# clouds_v30.net
KiCad netlist of a schematic drawn in EAGLE
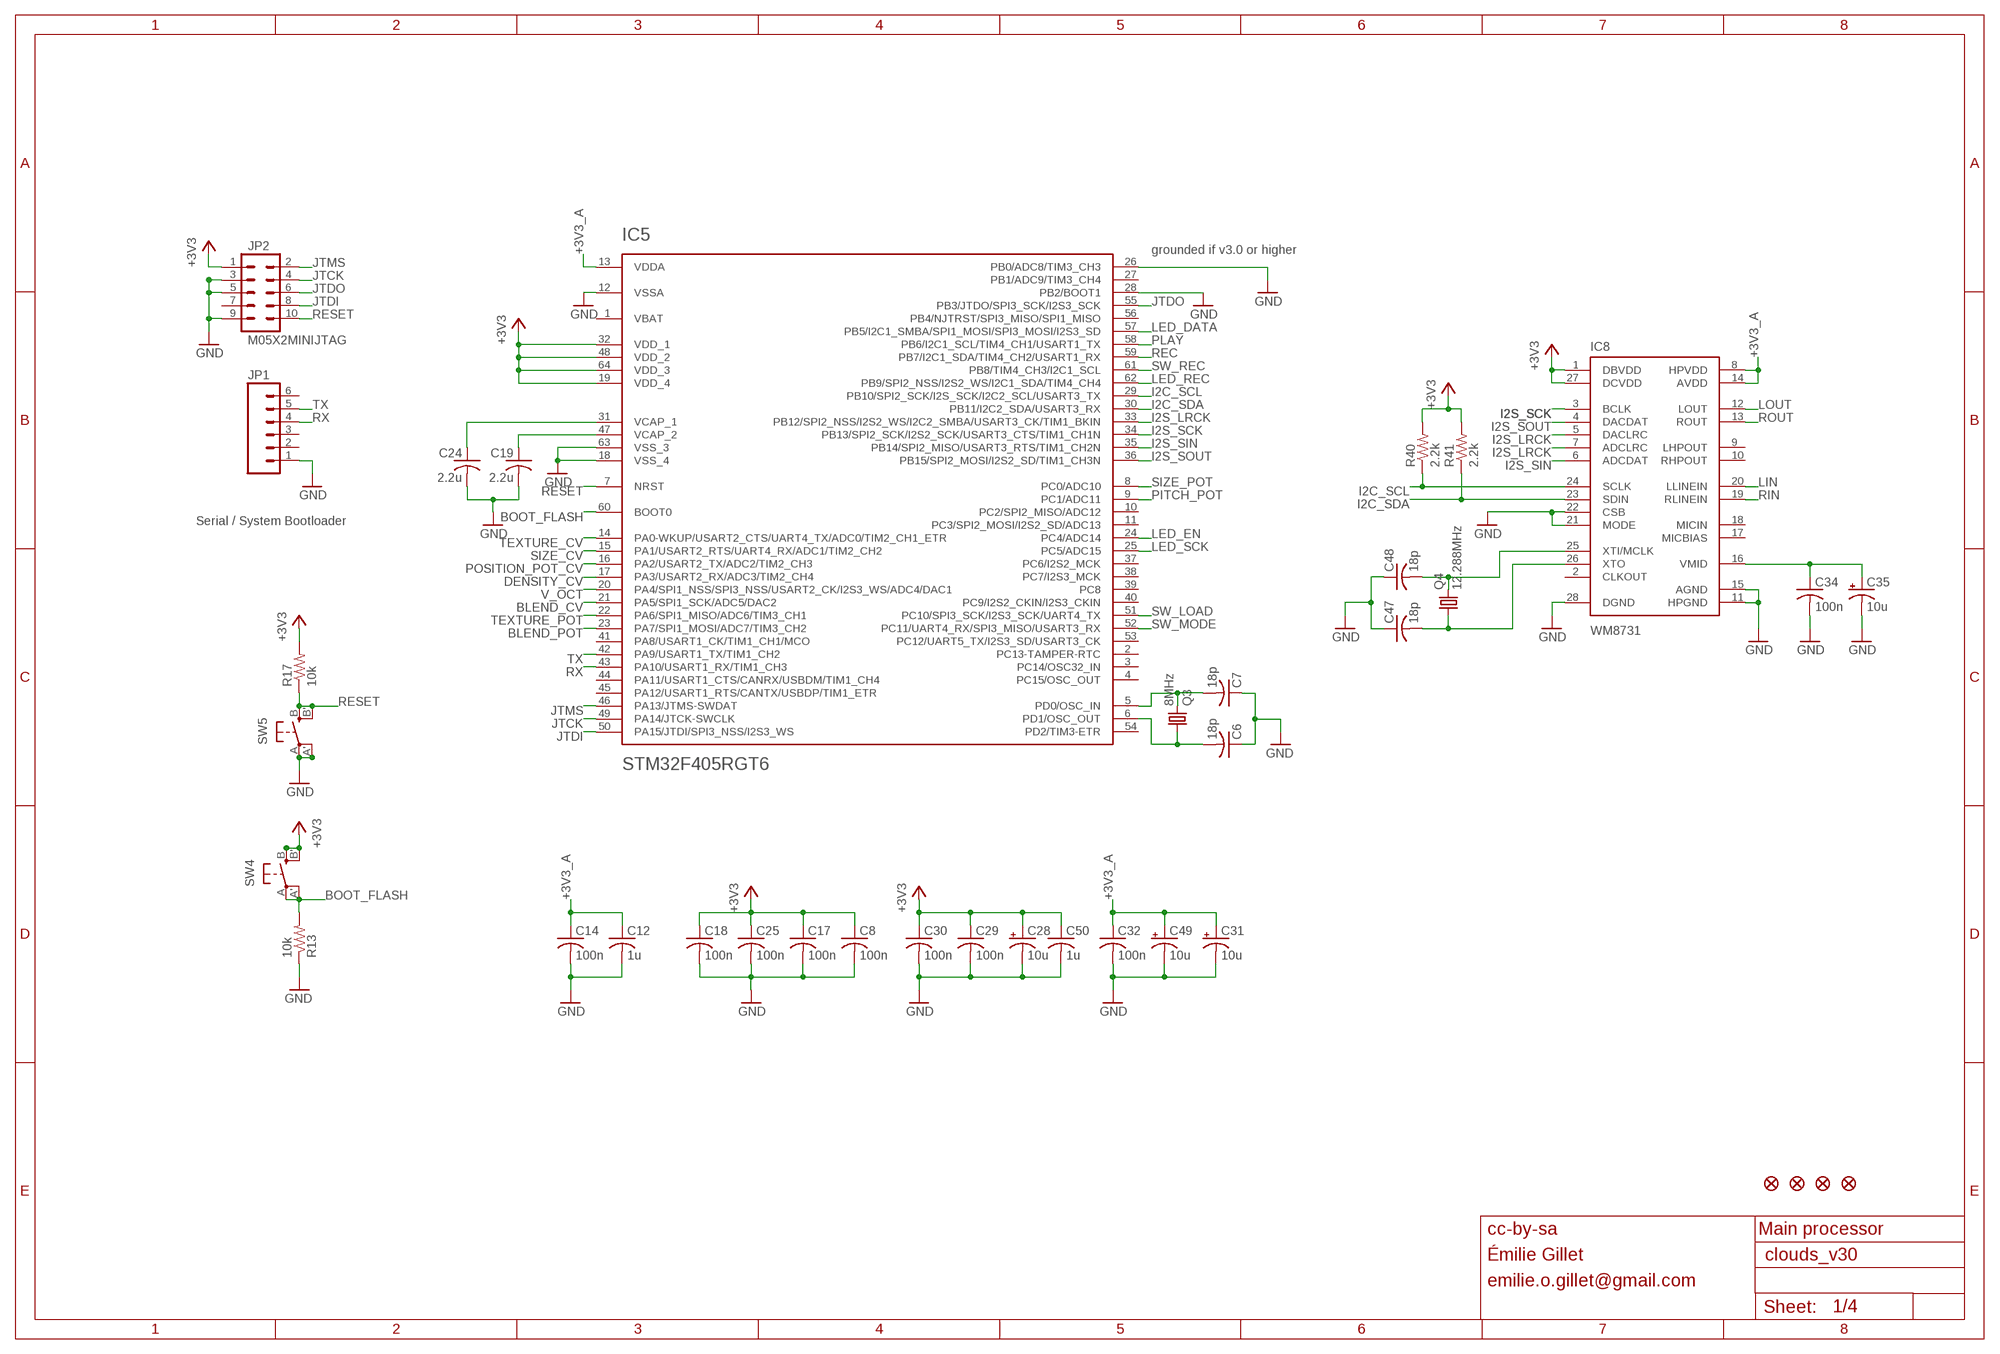
[diagram p0: schematic, sheet 1]
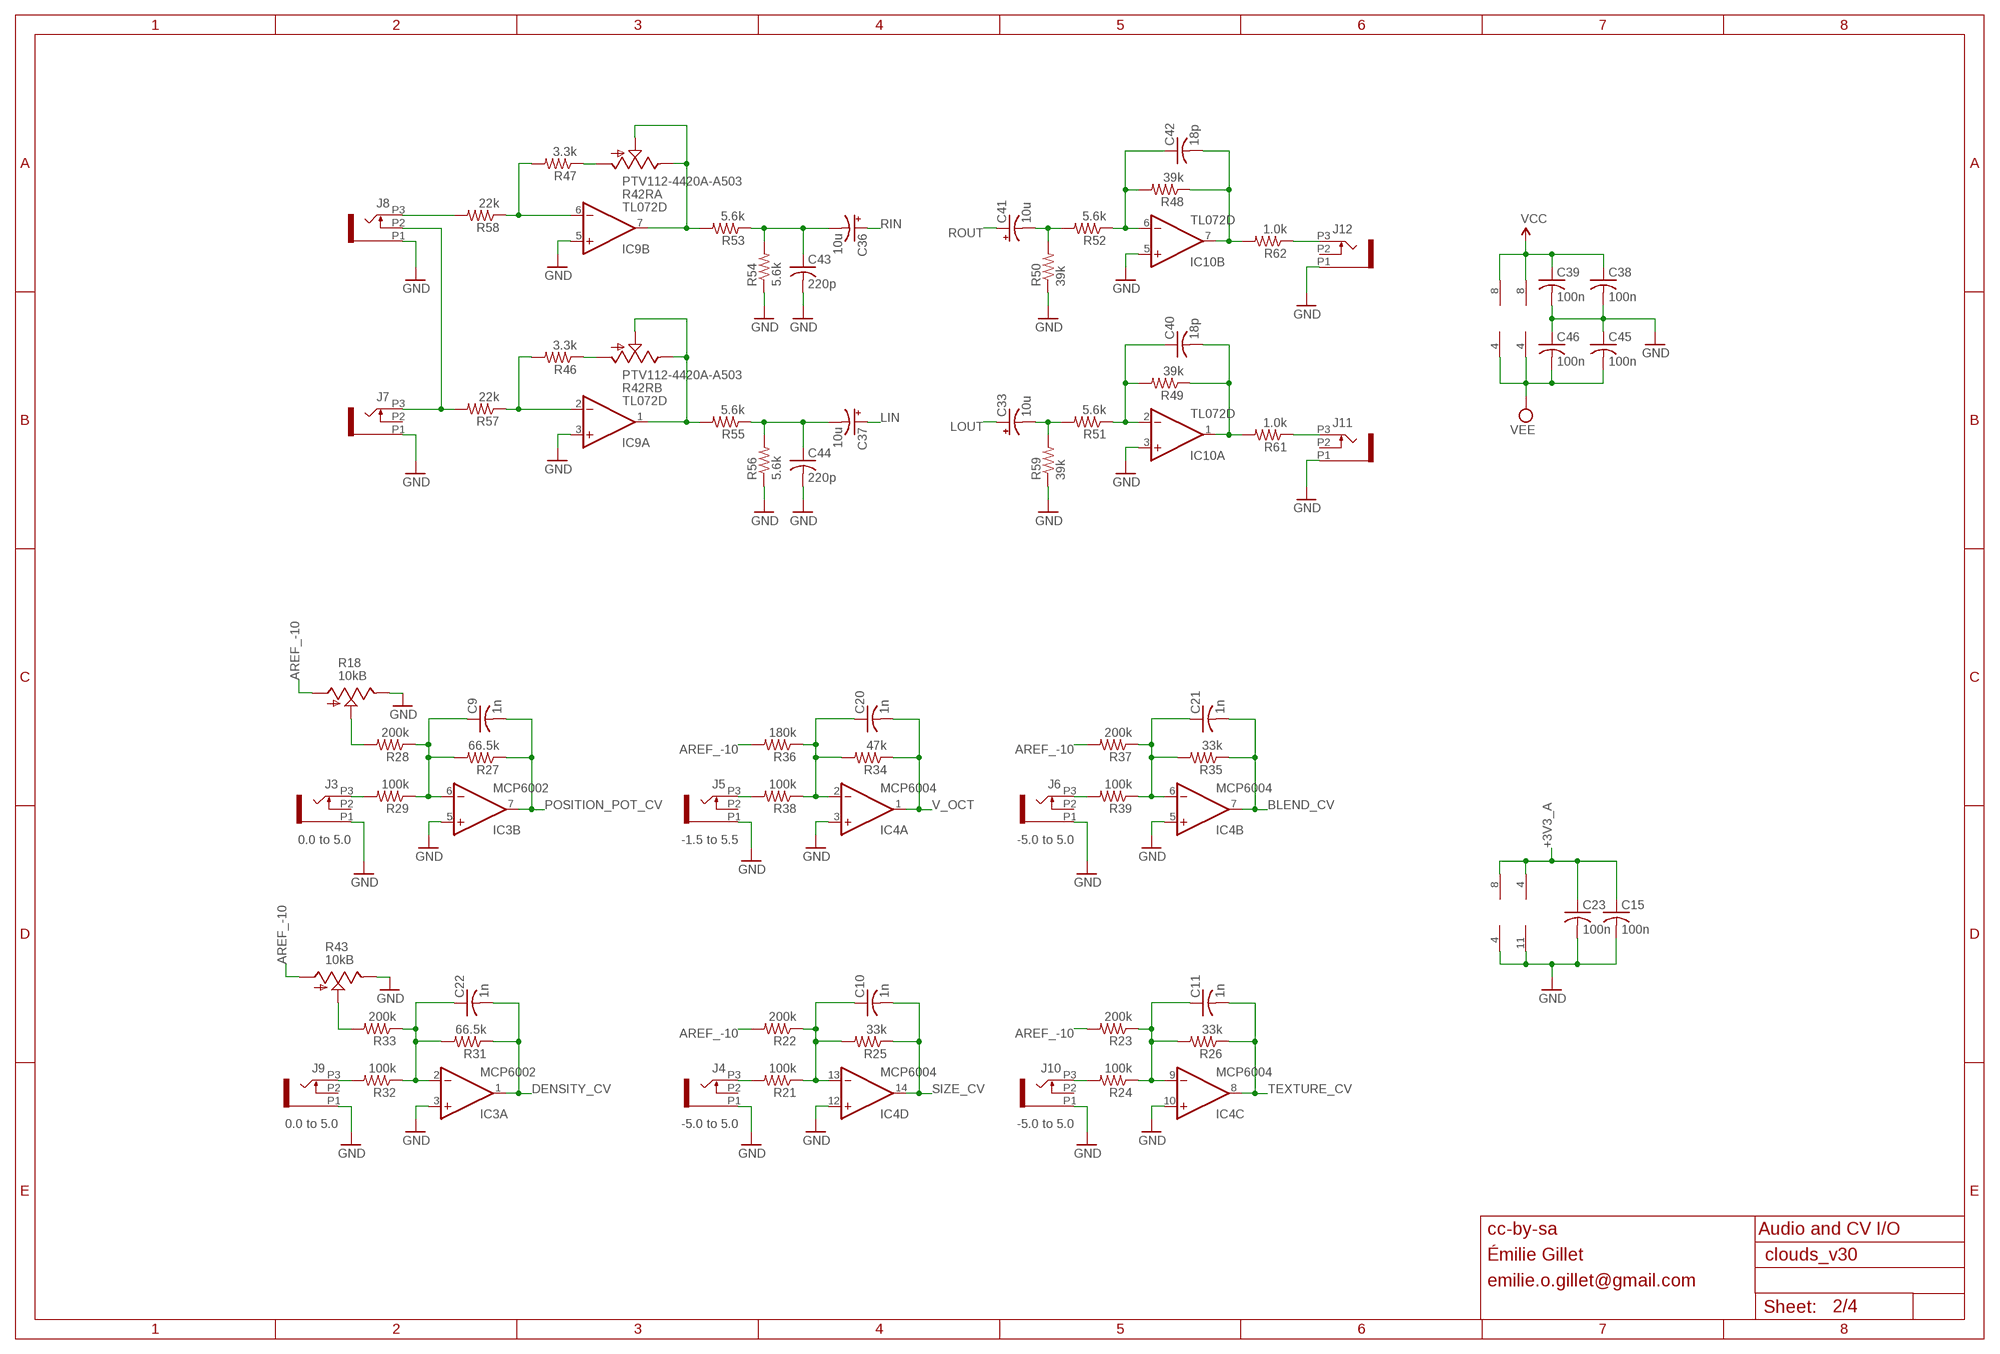
[diagram p1: schematic, sheet 2]
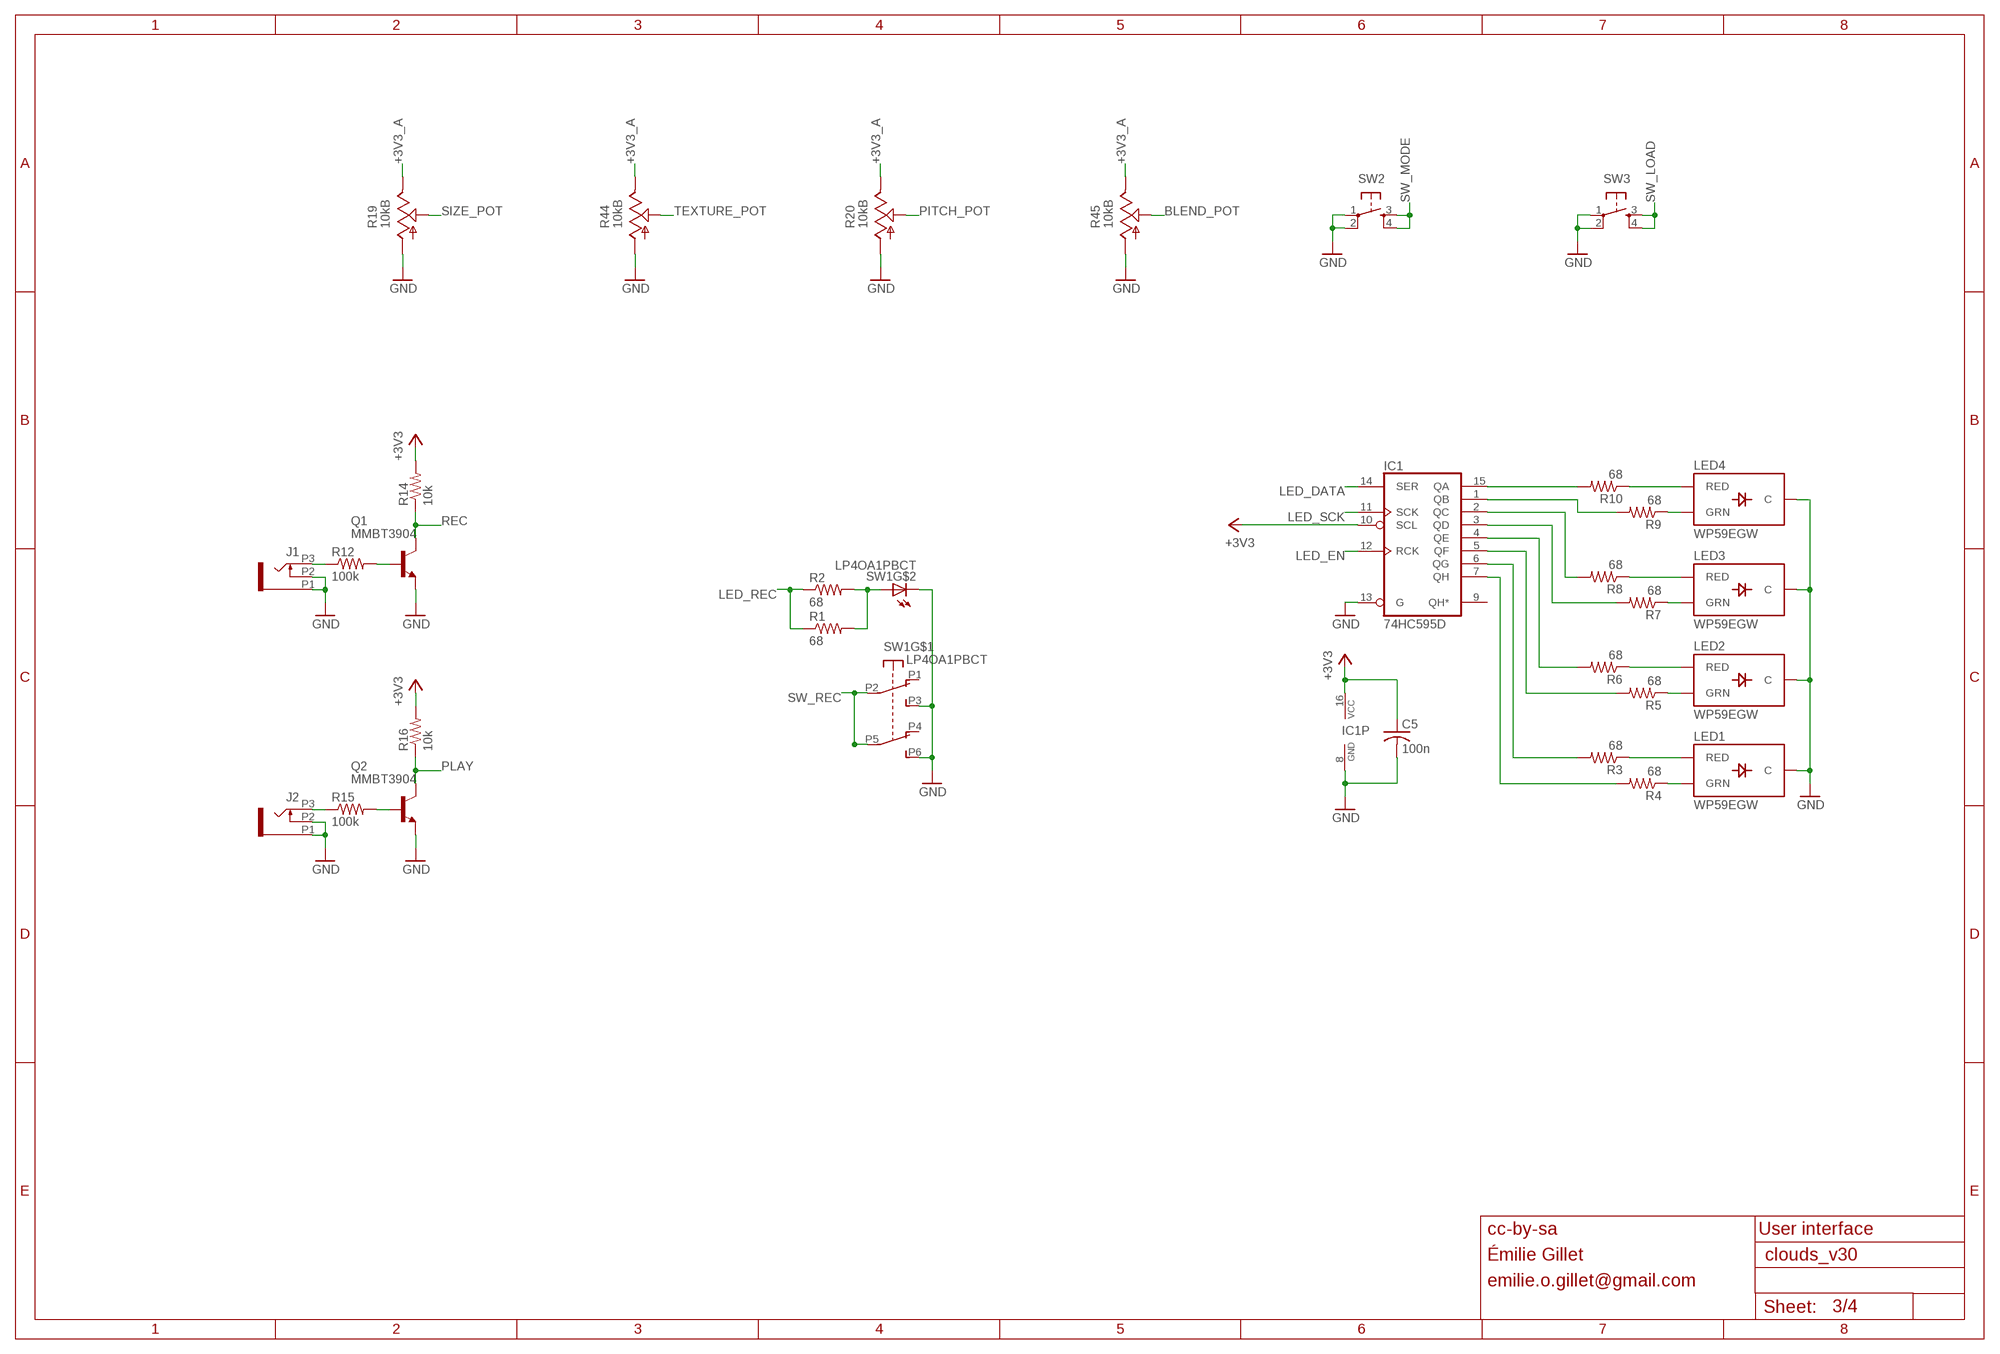
[diagram p2: schematic, sheet 3]
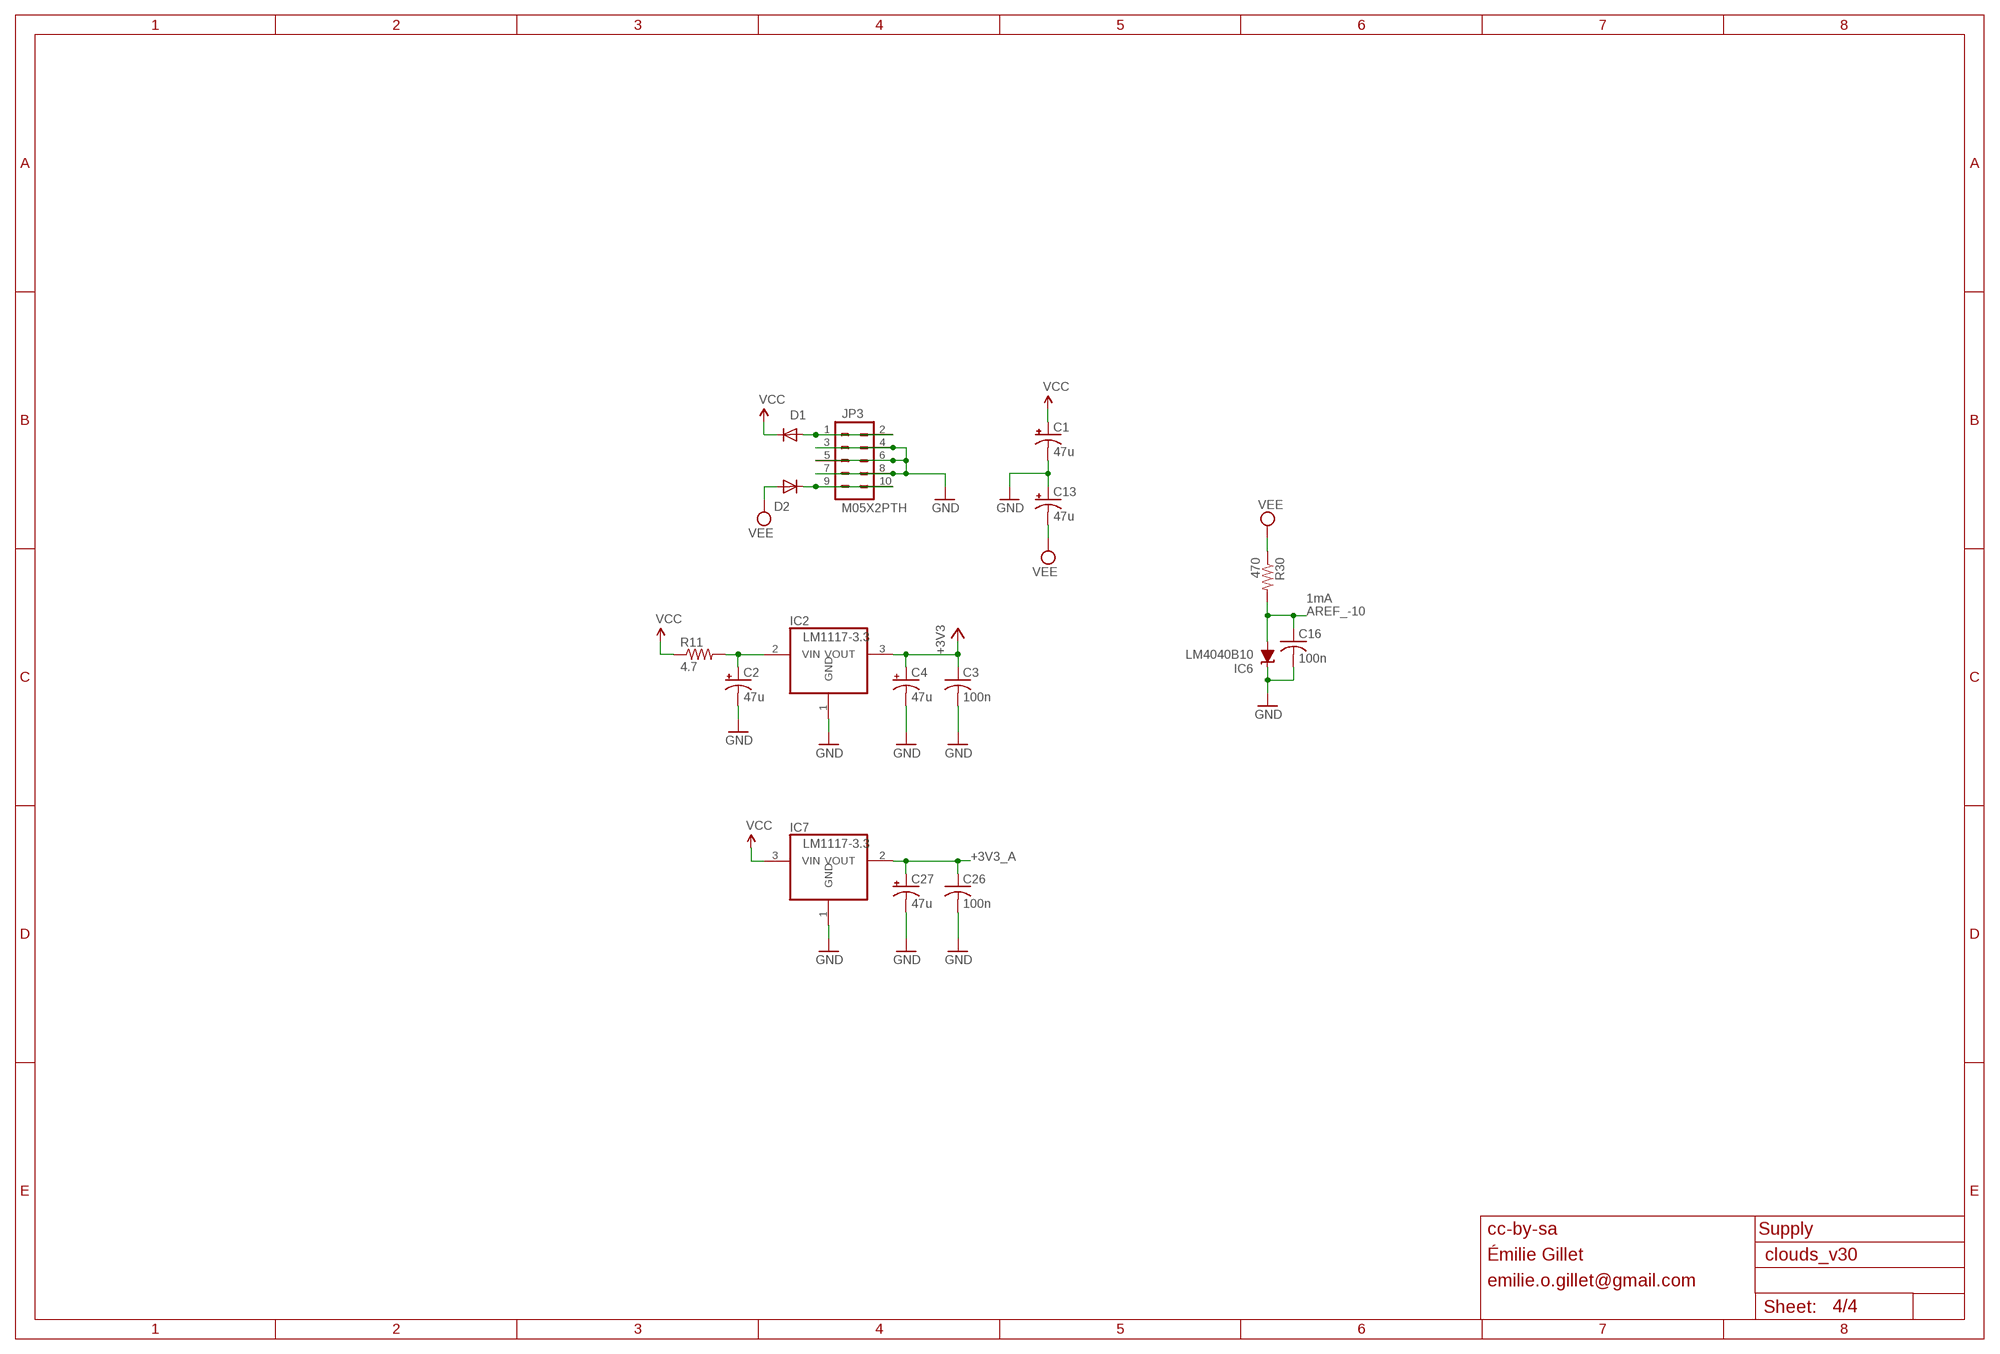
[diagram p3: schematic, sheet 4]

(export (version "E")
  (design (tool "Eeschema 10.0.6"))
  (components
    (comp (ref "C9")
      (value "1n")
      (footprint "eagle-import:C0603")
      (libsource (lib "eagle-import") (part "C-USC0603"))
    )
    (comp (ref "C10")
      (value "1n")
      (footprint "eagle-import:C0603")
      (libsource (lib "eagle-import") (part "C-USC0603"))
    )
    (comp (ref "C11")
      (value "1n")
      (footprint "eagle-import:C0603")
      (libsource (lib "eagle-import") (part "C-USC0603"))
    )
    (comp (ref "C15")
      (value "100n")
      (footprint "eagle-import:C0603")
      (libsource (lib "eagle-import") (part "C-USC0603"))
    )
    (comp (ref "C20")
      (value "1n")
      (footprint "eagle-import:C0603")
      (libsource (lib "eagle-import") (part "C-USC0603"))
    )
    (comp (ref "C21")
      (value "1n")
      (footprint "eagle-import:C0603")
      (libsource (lib "eagle-import") (part "C-USC0603"))
    )
    (comp (ref "C22")
      (value "1n")
      (footprint "eagle-import:C0603")
      (libsource (lib "eagle-import") (part "C-USC0603"))
    )
    (comp (ref "C23")
      (value "100n")
      (footprint "eagle-import:C0603")
      (libsource (lib "eagle-import") (part "C-USC0603"))
    )
    (comp (ref "C33")
      (value "10u")
      (footprint "eagle-import:PANASONIC_B")
      (libsource (lib "eagle-import") (part "CPOL-USB"))
    )
    (comp (ref "C36")
      (value "10u")
      (footprint "eagle-import:PANASONIC_B")
      (libsource (lib "eagle-import") (part "CPOL-USB"))
    )
    (comp (ref "C37")
      (value "10u")
      (footprint "eagle-import:PANASONIC_B")
      (libsource (lib "eagle-import") (part "CPOL-USB"))
    )
    (comp (ref "C38")
      (value "100n")
      (footprint "eagle-import:C0603")
      (libsource (lib "eagle-import") (part "C-USC0603"))
    )
    (comp (ref "C39")
      (value "100n")
      (footprint "eagle-import:C0603")
      (libsource (lib "eagle-import") (part "C-USC0603"))
    )
    (comp (ref "C40")
      (value "18p")
      (footprint "eagle-import:C0603")
      (libsource (lib "eagle-import") (part "C-USC0603"))
    )
    (comp (ref "C41")
      (value "10u")
      (footprint "eagle-import:PANASONIC_B")
      (libsource (lib "eagle-import") (part "CPOL-USB"))
    )
    (comp (ref "C42")
      (value "18p")
      (footprint "eagle-import:C0603")
      (libsource (lib "eagle-import") (part "C-USC0603"))
    )
    (comp (ref "C43")
      (value "220p")
      (footprint "eagle-import:C0603")
      (libsource (lib "eagle-import") (part "C-USC0603"))
    )
    (comp (ref "C44")
      (value "220p")
      (footprint "eagle-import:C0603")
      (libsource (lib "eagle-import") (part "C-USC0603"))
    )
    (comp (ref "C45")
      (value "100n")
      (footprint "eagle-import:C0603")
      (libsource (lib "eagle-import") (part "C-USC0603"))
    )
    (comp (ref "C46")
      (value "100n")
      (footprint "eagle-import:C0603")
      (libsource (lib "eagle-import") (part "C-USC0603"))
    )
    (comp (ref "IC3")
      (value "MCP6002")
      (footprint "eagle-import:SO08")
      (libsource (lib "eagle-import") (part "TL072D"))
    )
    (comp (ref "IC4")
      (value "MCP6004")
      (footprint "eagle-import:SO14")
      (libsource (lib "eagle-import") (part "TL074D"))
    )
    (comp (ref "IC9")
      (value "TL072D")
      (footprint "eagle-import:SO08")
      (libsource (lib "eagle-import") (part "og-linear_TL072D"))
    )
    (comp (ref "IC10")
      (value "TL072D")
      (footprint "eagle-import:SO08")
      (libsource (lib "eagle-import") (part "og-linear_TL072D"))
    )
    (comp (ref "J3")
      (value "PJ301_THONKICONN6")
      (footprint "eagle-import:WQP_PJ_301M6")
      (libsource (lib "eagle-import") (part "PJ301_THONKICONN6"))
    )
    (comp (ref "J4")
      (value "PJ301_THONKICONN6")
      (footprint "eagle-import:WQP_PJ_301M6")
      (libsource (lib "eagle-import") (part "PJ301_THONKICONN6"))
    )
    (comp (ref "J5")
      (value "PJ301_THONKICONN6")
      (footprint "eagle-import:WQP_PJ_301M6")
      (libsource (lib "eagle-import") (part "PJ301_THONKICONN6"))
    )
    (comp (ref "J6")
      (value "PJ301_THONKICONN6")
      (footprint "eagle-import:WQP_PJ_301M6")
      (libsource (lib "eagle-import") (part "PJ301_THONKICONN6"))
    )
    (comp (ref "J7")
      (value "PJ301_THONKICONN6")
      (footprint "eagle-import:WQP_PJ_301M6")
      (libsource (lib "eagle-import") (part "PJ301_THONKICONN6"))
    )
    (comp (ref "J8")
      (value "PJ301_THONKICONN6")
      (footprint "eagle-import:WQP_PJ_301M6")
      (libsource (lib "eagle-import") (part "PJ301_THONKICONN6"))
    )
    (comp (ref "J9")
      (value "PJ301_THONKICONN6")
      (footprint "eagle-import:WQP_PJ_301M6")
      (libsource (lib "eagle-import") (part "PJ301_THONKICONN6"))
    )
    (comp (ref "J10")
      (value "PJ301_THONKICONN6")
      (footprint "eagle-import:WQP_PJ_301M6")
      (libsource (lib "eagle-import") (part "PJ301_THONKICONN6"))
    )
    (comp (ref "J11")
      (value "PJ301_THONKICONN6")
      (footprint "eagle-import:WQP_PJ_301M6")
      (libsource (lib "eagle-import") (part "PJ301_THONKICONN6"))
    )
    (comp (ref "J12")
      (value "PJ301_THONKICONN6")
      (footprint "eagle-import:WQP_PJ_301M6")
      (libsource (lib "eagle-import") (part "PJ301_THONKICONN6"))
    )
    (comp (ref "R18")
      (value "10kB")
      (footprint "eagle-import:ALPS_POT_VERTICAL_PS")
      (libsource (lib "eagle-import") (part "POT_USVERTICAL_PS"))
    )
    (comp (ref "R21")
      (value "100k")
      (footprint "eagle-import:R0603")
      (libsource (lib "eagle-import") (part "R-US_R0603"))
    )
    (comp (ref "R22")
      (value "200k")
      (footprint "eagle-import:R0603")
      (libsource (lib "eagle-import") (part "R-US_R0603"))
    )
    (comp (ref "R23")
      (value "200k")
      (footprint "eagle-import:R0603")
      (libsource (lib "eagle-import") (part "R-US_R0603"))
    )
    (comp (ref "R24")
      (value "100k")
      (footprint "eagle-import:R0603")
      (libsource (lib "eagle-import") (part "R-US_R0603"))
    )
    (comp (ref "R25")
      (value "33k")
      (footprint "eagle-import:R0603")
      (libsource (lib "eagle-import") (part "R-US_R0603"))
    )
    (comp (ref "R26")
      (value "33k")
      (footprint "eagle-import:R0603")
      (libsource (lib "eagle-import") (part "R-US_R0603"))
    )
    (comp (ref "R27")
      (value "66.5k")
      (footprint "eagle-import:R0603")
      (libsource (lib "eagle-import") (part "R-US_R0603"))
    )
    (comp (ref "R28")
      (value "200k")
      (footprint "eagle-import:R0603")
      (libsource (lib "eagle-import") (part "R-US_R0603"))
    )
    (comp (ref "R29")
      (value "100k")
      (footprint "eagle-import:R0603")
      (libsource (lib "eagle-import") (part "R-US_R0603"))
    )
    (comp (ref "R31")
      (value "66.5k")
      (footprint "eagle-import:R0603")
      (libsource (lib "eagle-import") (part "R-US_R0603"))
    )
    (comp (ref "R32")
      (value "100k")
      (footprint "eagle-import:R0603")
      (libsource (lib "eagle-import") (part "R-US_R0603"))
    )
    (comp (ref "R33")
      (value "200k")
      (footprint "eagle-import:R0603")
      (libsource (lib "eagle-import") (part "R-US_R0603"))
    )
    (comp (ref "R34")
      (value "47k")
      (footprint "eagle-import:R0603")
      (libsource (lib "eagle-import") (part "R-US_R0603"))
    )
    (comp (ref "R35")
      (value "33k")
      (footprint "eagle-import:R0603")
      (libsource (lib "eagle-import") (part "R-US_R0603"))
    )
    (comp (ref "R36")
      (value "180k")
      (footprint "eagle-import:R0603")
      (libsource (lib "eagle-import") (part "R-US_R0603"))
    )
    (comp (ref "R37")
      (value "200k")
      (footprint "eagle-import:R0603")
      (libsource (lib "eagle-import") (part "R-US_R0603"))
    )
    (comp (ref "R38")
      (value "100k")
      (footprint "eagle-import:R0603")
      (libsource (lib "eagle-import") (part "R-US_R0603"))
    )
    (comp (ref "R39")
      (value "100k")
      (footprint "eagle-import:R0603")
      (libsource (lib "eagle-import") (part "R-US_R0603"))
    )
    (comp (ref "R42")
      (value "PTV112-4420A-A503")
      (footprint "eagle-import:BOURNS_PTV112")
      (libsource (lib "eagle-import") (part "POT_US_DUAL_GANG"))
    )
    (comp (ref "R43")
      (value "10kB")
      (footprint "eagle-import:ALPS_POT_VERTICAL_PS")
      (libsource (lib "eagle-import") (part "POT_USVERTICAL_PS"))
    )
    (comp (ref "R46")
      (value "3.3k")
      (footprint "eagle-import:R0603")
      (libsource (lib "eagle-import") (part "R-US_R0603"))
    )
    (comp (ref "R47")
      (value "3.3k")
      (footprint "eagle-import:R0603")
      (libsource (lib "eagle-import") (part "R-US_R0603"))
    )
    (comp (ref "R48")
      (value "39k")
      (footprint "eagle-import:R0603")
      (libsource (lib "eagle-import") (part "R-US_R0603"))
    )
    (comp (ref "R49")
      (value "39k")
      (footprint "eagle-import:R0603")
      (libsource (lib "eagle-import") (part "R-US_R0603"))
    )
    (comp (ref "R50")
      (value "39k")
      (footprint "eagle-import:R0603")
      (libsource (lib "eagle-import") (part "R-US_R0603"))
    )
    (comp (ref "R51")
      (value "5.6k")
      (footprint "eagle-import:R0603")
      (libsource (lib "eagle-import") (part "R-US_R0603"))
    )
    (comp (ref "R52")
      (value "5.6k")
      (footprint "eagle-import:R0603")
      (libsource (lib "eagle-import") (part "R-US_R0603"))
    )
    (comp (ref "R53")
      (value "5.6k")
      (footprint "eagle-import:R0603")
      (libsource (lib "eagle-import") (part "R-US_R0603"))
    )
    (comp (ref "R54")
      (value "5.6k")
      (footprint "eagle-import:R0603")
      (libsource (lib "eagle-import") (part "R-US_R0603"))
    )
    (comp (ref "R55")
      (value "5.6k")
      (footprint "eagle-import:R0603")
      (libsource (lib "eagle-import") (part "R-US_R0603"))
    )
    (comp (ref "R56")
      (value "5.6k")
      (footprint "eagle-import:R0603")
      (libsource (lib "eagle-import") (part "R-US_R0603"))
    )
    (comp (ref "R57")
      (value "22k")
      (footprint "eagle-import:R0603")
      (libsource (lib "eagle-import") (part "R-US_R0603"))
    )
    (comp (ref "R58")
      (value "22k")
      (footprint "eagle-import:R0603")
      (libsource (lib "eagle-import") (part "R-US_R0603"))
    )
    (comp (ref "R59")
      (value "39k")
      (footprint "eagle-import:R0603")
      (libsource (lib "eagle-import") (part "R-US_R0603"))
    )
    (comp (ref "R61")
      (value "1.0k")
      (footprint "eagle-import:R0603")
      (libsource (lib "eagle-import") (part "R-US_R0603"))
    )
    (comp (ref "R62")
      (value "1.0k")
      (footprint "eagle-import:R0603")
      (libsource (lib "eagle-import") (part "R-US_R0603"))
    )
    (comp (ref "C5")
      (value "100n")
      (footprint "eagle-import:C0603")
      (libsource (lib "eagle-import") (part "C-USC0603"))
    )
    (comp (ref "IC1")
      (value "74HC595D")
      (footprint "eagle-import:SO16")
      (libsource (lib "eagle-import") (part "74595DHC"))
    )
    (comp (ref "J1")
      (value "PJ301_THONKICONN6")
      (footprint "eagle-import:WQP_PJ_301M6")
      (libsource (lib "eagle-import") (part "PJ301_THONKICONN6"))
    )
    (comp (ref "J2")
      (value "PJ301_THONKICONN6")
      (footprint "eagle-import:WQP_PJ_301M6")
      (libsource (lib "eagle-import") (part "PJ301_THONKICONN6"))
    )
    (comp (ref "LED1")
      (value "WP59EGW")
      (footprint "eagle-import:LED-BICOLOR-THROUGHHOLE-5MM")
      (libsource (lib "eagle-import") (part "LED-BICOLOR-THROUGHHOLE5MM"))
    )
    (comp (ref "LED2")
      (value "WP59EGW")
      (footprint "eagle-import:LED-BICOLOR-THROUGHHOLE-5MM")
      (libsource (lib "eagle-import") (part "LED-BICOLOR-THROUGHHOLE5MM"))
    )
    (comp (ref "LED3")
      (value "WP59EGW")
      (footprint "eagle-import:LED-BICOLOR-THROUGHHOLE-5MM")
      (libsource (lib "eagle-import") (part "LED-BICOLOR-THROUGHHOLE5MM"))
    )
    (comp (ref "LED4")
      (value "WP59EGW")
      (footprint "eagle-import:LED-BICOLOR-THROUGHHOLE-5MM")
      (libsource (lib "eagle-import") (part "LED-BICOLOR-THROUGHHOLE5MM"))
    )
    (comp (ref "Q1")
      (value "MMBT3904")
      (footprint "eagle-import:SOT23-BEC")
      (libsource (lib "eagle-import") (part "-NPN-SOT23-BECMMBT3904LT1"))
    )
    (comp (ref "Q2")
      (value "MMBT3904")
      (footprint "eagle-import:SOT23-BEC")
      (libsource (lib "eagle-import") (part "-NPN-SOT23-BECMMBT3904LT1"))
    )
    (comp (ref "R1")
      (value "68")
      (footprint "eagle-import:R0603")
      (libsource (lib "eagle-import") (part "R-US_R0603"))
    )
    (comp (ref "R2")
      (value "68")
      (footprint "eagle-import:R0603")
      (libsource (lib "eagle-import") (part "R-US_R0603"))
    )
    (comp (ref "R3")
      (value "68")
      (footprint "eagle-import:R0603")
      (libsource (lib "eagle-import") (part "R-US_R0603"))
    )
    (comp (ref "R4")
      (value "68")
      (footprint "eagle-import:R0603")
      (libsource (lib "eagle-import") (part "R-US_R0603"))
    )
    (comp (ref "R5")
      (value "68")
      (footprint "eagle-import:R0603")
      (libsource (lib "eagle-import") (part "R-US_R0603"))
    )
    (comp (ref "R6")
      (value "68")
      (footprint "eagle-import:R0603")
      (libsource (lib "eagle-import") (part "R-US_R0603"))
    )
    (comp (ref "R7")
      (value "68")
      (footprint "eagle-import:R0603")
      (libsource (lib "eagle-import") (part "R-US_R0603"))
    )
    (comp (ref "R8")
      (value "68")
      (footprint "eagle-import:R0603")
      (libsource (lib "eagle-import") (part "R-US_R0603"))
    )
    (comp (ref "R9")
      (value "68")
      (footprint "eagle-import:R0603")
      (libsource (lib "eagle-import") (part "R-US_R0603"))
    )
    (comp (ref "R10")
      (value "68")
      (footprint "eagle-import:R0603")
      (libsource (lib "eagle-import") (part "R-US_R0603"))
    )
    (comp (ref "R12")
      (value "100k")
      (footprint "eagle-import:R0603")
      (libsource (lib "eagle-import") (part "R-US_R0603"))
    )
    (comp (ref "R14")
      (value "10k")
      (footprint "eagle-import:R0603")
      (libsource (lib "eagle-import") (part "R-US_R0603"))
    )
    (comp (ref "R15")
      (value "100k")
      (footprint "eagle-import:R0603")
      (libsource (lib "eagle-import") (part "R-US_R0603"))
    )
    (comp (ref "R16")
      (value "10k")
      (footprint "eagle-import:R0603")
      (libsource (lib "eagle-import") (part "R-US_R0603"))
    )
    (comp (ref "R19")
      (value "10kB")
      (footprint "eagle-import:ALPS_POT_VERTICAL_PS")
      (libsource (lib "eagle-import") (part "POT_USVERTICAL_PS"))
    )
    (comp (ref "R20")
      (value "10kB")
      (footprint "eagle-import:ALPS_POT_VERTICAL_PS")
      (libsource (lib "eagle-import") (part "POT_USVERTICAL_PS"))
    )
    (comp (ref "R44")
      (value "10kB")
      (footprint "eagle-import:ALPS_POT_VERTICAL_PS")
      (libsource (lib "eagle-import") (part "POT_USVERTICAL_PS"))
    )
    (comp (ref "R45")
      (value "10kB")
      (footprint "eagle-import:ALPS_POT_VERTICAL_PS")
      (libsource (lib "eagle-import") (part "POT_USVERTICAL_PS"))
    )
    (comp (ref "SW1")
      (value "LP4OA1PBCT")
      (footprint "eagle-import:LP4OA1PBCT")
      (libsource (lib "eagle-import") (part "LP4OA1PBCT"))
    )
    (comp (ref "SW2")
      (value "TAC_SWITCHPTH")
      (footprint "eagle-import:TACTILE-PTH")
      (libsource (lib "eagle-import") (part "TAC_SWITCHPTH"))
    )
    (comp (ref "SW3")
      (value "TAC_SWITCHPTH")
      (footprint "eagle-import:TACTILE-PTH")
      (libsource (lib "eagle-import") (part "TAC_SWITCHPTH"))
    )
    (comp (ref "C6")
      (value "18p")
      (footprint "eagle-import:C0603")
      (libsource (lib "eagle-import") (part "C-USC0603"))
    )
    (comp (ref "C7")
      (value "18p")
      (footprint "eagle-import:C0603")
      (libsource (lib "eagle-import") (part "C-USC0603"))
    )
    (comp (ref "C8")
      (value "100n")
      (footprint "eagle-import:C0603")
      (libsource (lib "eagle-import") (part "C-USC0603"))
    )
    (comp (ref "C12")
      (value "1u")
      (footprint "eagle-import:C0603")
      (libsource (lib "eagle-import") (part "C-USC0603"))
    )
    (comp (ref "C14")
      (value "100n")
      (footprint "eagle-import:C0603")
      (libsource (lib "eagle-import") (part "C-USC0603"))
    )
    (comp (ref "C17")
      (value "100n")
      (footprint "eagle-import:C0603")
      (libsource (lib "eagle-import") (part "C-USC0603"))
    )
    (comp (ref "C18")
      (value "100n")
      (footprint "eagle-import:C0603")
      (libsource (lib "eagle-import") (part "C-USC0603"))
    )
    (comp (ref "C19")
      (value "2.2u")
      (footprint "eagle-import:C0805")
      (libsource (lib "eagle-import") (part "C-USC0805"))
    )
    (comp (ref "C24")
      (value "2.2u")
      (footprint "eagle-import:C0805")
      (libsource (lib "eagle-import") (part "C-USC0805"))
    )
    (comp (ref "C25")
      (value "100n")
      (footprint "eagle-import:C0603")
      (libsource (lib "eagle-import") (part "C-USC0603"))
    )
    (comp (ref "C28")
      (value "10u")
      (footprint "eagle-import:PANASONIC_A")
      (libsource (lib "eagle-import") (part "CPOL-USA"))
    )
    (comp (ref "C29")
      (value "100n")
      (footprint "eagle-import:C0603")
      (libsource (lib "eagle-import") (part "C-USC0603"))
    )
    (comp (ref "C30")
      (value "100n")
      (footprint "eagle-import:C0603")
      (libsource (lib "eagle-import") (part "C-USC0603"))
    )
    (comp (ref "C31")
      (value "10u")
      (footprint "eagle-import:PANASONIC_B")
      (libsource (lib "eagle-import") (part "CPOL-USB"))
    )
    (comp (ref "C32")
      (value "100n")
      (footprint "eagle-import:C0603")
      (libsource (lib "eagle-import") (part "C-USC0603"))
    )
    (comp (ref "C34")
      (value "100n")
      (footprint "eagle-import:C0603")
      (libsource (lib "eagle-import") (part "C-USC0603"))
    )
    (comp (ref "C35")
      (value "10u")
      (footprint "eagle-import:PANASONIC_B")
      (libsource (lib "eagle-import") (part "CPOL-USB"))
    )
    (comp (ref "C47")
      (value "18p")
      (footprint "eagle-import:C0603")
      (libsource (lib "eagle-import") (part "C-USC0603"))
    )
    (comp (ref "C48")
      (value "18p")
      (footprint "eagle-import:C0603")
      (libsource (lib "eagle-import") (part "C-USC0603"))
    )
    (comp (ref "C49")
      (value "10u")
      (footprint "eagle-import:PANASONIC_A")
      (libsource (lib "eagle-import") (part "CPOL-USA"))
    )
    (comp (ref "C50")
      (value "1u")
      (footprint "eagle-import:C0603")
      (libsource (lib "eagle-import") (part "C-USC0603"))
    )
    (comp (ref "F1")
      (value "FIDUCIAL1X2")
      (footprint "eagle-import:FIDUCIAL-1X2")
      (libsource (lib "eagle-import") (part "FIDUCIAL1X2"))
    )
    (comp (ref "F2")
      (value "FIDUCIAL1X2")
      (footprint "eagle-import:FIDUCIAL-1X2")
      (libsource (lib "eagle-import") (part "FIDUCIAL1X2"))
    )
    (comp (ref "F3")
      (value "FIDUCIAL1X2")
      (footprint "eagle-import:FIDUCIAL-1X2")
      (libsource (lib "eagle-import") (part "FIDUCIAL1X2"))
    )
    (comp (ref "F4")
      (value "FIDUCIAL1X2")
      (footprint "eagle-import:FIDUCIAL-1X2")
      (libsource (lib "eagle-import") (part "FIDUCIAL1X2"))
    )
    (comp (ref "IC5")
      (value "STM32F405RGT6")
      (footprint "eagle-import:TQFP-10X10-64")
      (libsource (lib "eagle-import") (part "STM32F20X"))
    )
    (comp (ref "IC8")
      (value "WM8731")
      (footprint "eagle-import:SSOP28")
      (libsource (lib "eagle-import") (part "WM8731"))
    )
    (comp (ref "JP1")
      (value "M06SIP")
      (footprint "eagle-import:1X06")
      (libsource (lib "eagle-import") (part "M06SIP"))
    )
    (comp (ref "JP2")
      (value "M05X2MINIJTAG")
      (footprint "eagle-import:2X5-1.27")
      (libsource (lib "eagle-import") (part "M05X2MINIJTAG"))
    )
    (comp (ref "Q3")
      (value "8MHz")
      (footprint "eagle-import:HC49UP")
      (libsource (lib "eagle-import") (part "CRYSTALHC49UP"))
    )
    (comp (ref "Q4")
      (value "12.288MHz")
      (footprint "eagle-import:HC49UP")
      (libsource (lib "eagle-import") (part "CRYSTALHC49UP"))
    )
    (comp (ref "R13")
      (value "10k")
      (footprint "eagle-import:R0603")
      (libsource (lib "eagle-import") (part "R-US_R0603"))
    )
    (comp (ref "R17")
      (value "10k")
      (footprint "eagle-import:R0603")
      (libsource (lib "eagle-import") (part "R-US_R0603"))
    )
    (comp (ref "R40")
      (value "2.2k")
      (footprint "eagle-import:R0603")
      (libsource (lib "eagle-import") (part "R-US_R0603"))
    )
    (comp (ref "R41")
      (value "2.2k")
      (footprint "eagle-import:R0603")
      (libsource (lib "eagle-import") (part "R-US_R0603"))
    )
    (comp (ref "SW4")
      (value "EVQQ2")
      (footprint "eagle-import:EVQ-Q2")
      (libsource (lib "eagle-import") (part "EVQQ2"))
    )
    (comp (ref "SW5")
      (value "EVQQ2")
      (footprint "eagle-import:EVQ-Q2")
      (libsource (lib "eagle-import") (part "EVQQ2"))
    )
    (comp (ref "C1")
      (value "47u")
      (footprint "eagle-import:PANASONIC_D")
      (libsource (lib "eagle-import") (part "CPOL-USD"))
    )
    (comp (ref "C2")
      (value "47u")
      (footprint "eagle-import:PANASONIC_D")
      (libsource (lib "eagle-import") (part "CPOL-USD"))
    )
    (comp (ref "C3")
      (value "100n")
      (footprint "eagle-import:C0603")
      (libsource (lib "eagle-import") (part "C-USC0603"))
    )
    (comp (ref "C4")
      (value "47u")
      (footprint "eagle-import:PANASONIC_D")
      (libsource (lib "eagle-import") (part "CPOL-USD"))
    )
    (comp (ref "C13")
      (value "47u")
      (footprint "eagle-import:PANASONIC_D")
      (libsource (lib "eagle-import") (part "CPOL-USD"))
    )
    (comp (ref "C16")
      (value "100n")
      (footprint "eagle-import:C0603")
      (libsource (lib "eagle-import") (part "C-USC0603"))
    )
    (comp (ref "C26")
      (value "100n")
      (footprint "eagle-import:C0603")
      (libsource (lib "eagle-import") (part "C-USC0603"))
    )
    (comp (ref "C27")
      (value "47u")
      (footprint "eagle-import:PANASONIC_D")
      (libsource (lib "eagle-import") (part "CPOL-USD"))
    )
    (comp (ref "D1")
      (value "1N5819HW")
      (footprint "eagle-import:SOD123")
      (libsource (lib "eagle-import") (part "DIODE-SOD123"))
    )
    (comp (ref "D2")
      (value "1N5819HW")
      (footprint "eagle-import:SOD123")
      (libsource (lib "eagle-import") (part "DIODE-SOD123"))
    )
    (comp (ref "IC2")
      (value "LM1117-3.3")
      (footprint "eagle-import:TO252")
      (libsource (lib "eagle-import") (part "REG1117T"))
    )
    (comp (ref "IC6")
      (value "LM4040B10")
      (footprint "eagle-import:DBZ_R-PDSO-G3")
      (libsource (lib "eagle-import") (part "LM4041DBZB12"))
    )
    (comp (ref "IC7")
      (value "LM1117-3.3")
      (footprint "eagle-import:SOT223")
      (libsource (lib "eagle-import") (part "REG1117"))
    )
    (comp (ref "JP3")
      (value "M05X2PTH")
      (footprint "eagle-import:AVR_ICSP")
      (libsource (lib "eagle-import") (part "M05X2PTH"))
    )
    (comp (ref "R11")
      (value "4.7")
      (footprint "eagle-import:R1206")
      (libsource (lib "eagle-import") (part "R-US_R1206"))
    )
    (comp (ref "R30")
      (value "470")
      (footprint "eagle-import:R0603")
      (libsource (lib "eagle-import") (part "R-US_R0603"))
    )
  )
  (nets
    (net (code "1") (name "+3V3") (class "Default")
      (node (ref "C17") (pin "1") (pinfunction "1_1") (pintype "passive"))
      (node (ref "C18") (pin "1") (pinfunction "1_1") (pintype "passive"))
      (node (ref "C25") (pin "1") (pinfunction "1_1") (pintype "passive"))
      (node (ref "C28") (pin "+") (pinfunction "+_+") (pintype "passive"))
      (node (ref "C29") (pin "1") (pinfunction "1_1") (pintype "passive"))
      (node (ref "C3") (pin "1") (pinfunction "1_1") (pintype "passive"))
      (node (ref "C30") (pin "1") (pinfunction "1_1") (pintype "passive"))
      (node (ref "C4") (pin "+") (pinfunction "+_+") (pintype "passive"))
      (node (ref "C5") (pin "1") (pinfunction "1_1") (pintype "passive"))
      (node (ref "C50") (pin "1") (pinfunction "1_1") (pintype "passive"))
      (node (ref "C8") (pin "1") (pinfunction "1_1") (pintype "passive"))
      (node (ref "IC1") (pin "10") (pinfunction "SCL_10") (pintype "input"))
      (node (ref "IC1") (pin "16") (pinfunction "VCC_16") (pintype "power_in"))
      (node (ref "IC2") (pin "3") (pinfunction "VOUT_3") (pintype "output"))
      (node (ref "IC5") (pin "19") (pinfunction "VDD_4_19") (pintype "power_in"))
      (node (ref "IC5") (pin "32") (pinfunction "VDD_1_32") (pintype "power_in"))
      (node (ref "IC5") (pin "48") (pinfunction "VDD_2_48") (pintype "power_in"))
      (node (ref "IC5") (pin "64") (pinfunction "VDD_3_64") (pintype "power_in"))
      (node (ref "IC8") (pin "1") (pinfunction "DBVDD_1") (pintype "bidirectional"))
      (node (ref "IC8") (pin "27") (pinfunction "DCVDD_27") (pintype "bidirectional"))
      (node (ref "JP2") (pin "1") (pinfunction "1_1") (pintype "passive"))
      (node (ref "R14") (pin "2") (pinfunction "2_2") (pintype "passive"))
      (node (ref "R16") (pin "2") (pinfunction "2_2") (pintype "passive"))
      (node (ref "R17") (pin "2") (pinfunction "2_2") (pintype "passive"))
      (node (ref "R40") (pin "2") (pinfunction "2_2") (pintype "passive"))
      (node (ref "R41") (pin "2") (pinfunction "2_2") (pintype "passive"))
      (node (ref "SW4") (pin "B") (pinfunction "S_B") (pintype "passive"))
      (node (ref "SW4") (pin "B'") (pinfunction "S1_B'") (pintype "passive"))
    )
    (net (code "2") (name "+3V3_A") (class "Default")
      (node (ref "C12") (pin "1") (pinfunction "1_1") (pintype "passive"))
      (node (ref "C14") (pin "1") (pinfunction "1_1") (pintype "passive"))
      (node (ref "C15") (pin "1") (pinfunction "1_1") (pintype "passive"))
      (node (ref "C23") (pin "1") (pinfunction "1_1") (pintype "passive"))
      (node (ref "C26") (pin "1") (pinfunction "1_1") (pintype "passive"))
      (node (ref "C27") (pin "+") (pinfunction "+_+") (pintype "passive"))
      (node (ref "C31") (pin "+") (pinfunction "+_+") (pintype "passive"))
      (node (ref "C32") (pin "1") (pinfunction "1_1") (pintype "passive"))
      (node (ref "C49") (pin "+") (pinfunction "+_+") (pintype "passive"))
      (node (ref "IC3") (pin "8") (pinfunction "V+_8") (pintype "power_in"))
      (node (ref "IC4") (pin "4") (pinfunction "V+_4") (pintype "power_in"))
      (node (ref "IC5") (pin "13") (pinfunction "VDDA_13") (pintype "power_in"))
      (node (ref "IC7") (pin "2") (pinfunction "VOUT_2") (pintype "output"))
      (node (ref "IC8") (pin "14") (pinfunction "AVDD_14") (pintype "bidirectional"))
      (node (ref "IC8") (pin "8") (pinfunction "HPVDD_8") (pintype "bidirectional"))
      (node (ref "R19") (pin "P$1") (pinfunction "E_P$1") (pintype "passive"))
      (node (ref "R20") (pin "P$1") (pinfunction "E_P$1") (pintype "passive"))
      (node (ref "R44") (pin "P$1") (pinfunction "E_P$1") (pintype "passive"))
      (node (ref "R45") (pin "P$1") (pinfunction "E_P$1") (pintype "passive"))
    )
    (net (code "3") (name "AREF_-10") (class "Default")
      (node (ref "C16") (pin "1") (pinfunction "1_1") (pintype "passive"))
      (node (ref "IC6") (pin "2") (pinfunction "A_2") (pintype "passive"))
      (node (ref "R18") (pin "P$3") (pinfunction "A_P$3") (pintype "passive"))
      (node (ref "R22") (pin "2") (pinfunction "2_2") (pintype "passive"))
      (node (ref "R23") (pin "2") (pinfunction "2_2") (pintype "passive"))
      (node (ref "R30") (pin "2") (pinfunction "2_2") (pintype "passive"))
      (node (ref "R36") (pin "2") (pinfunction "2_2") (pintype "passive"))
      (node (ref "R37") (pin "2") (pinfunction "2_2") (pintype "passive"))
      (node (ref "R43") (pin "P$3") (pinfunction "A_P$3") (pintype "passive"))
    )
    (net (code "4") (name "BLEND_CV") (class "Default")
      (node (ref "C21") (pin "2") (pinfunction "2_2") (pintype "passive"))
      (node (ref "IC4") (pin "7") (pinfunction "OUT_7") (pintype "output"))
      (node (ref "IC5") (pin "21") (pinfunction "PA5/SPI1_SCK/ADC5/DAC2_21") (pintype "bidirectional"))
      (node (ref "R35") (pin "1") (pinfunction "1_1") (pintype "passive"))
    )
    (net (code "5") (name "BLEND_POT") (class "Default")
      (node (ref "IC5") (pin "23") (pinfunction "PA7/SPI1_MOSI/ADC7/TIM3_CH2_23") (pintype "bidirectional"))
      (node (ref "R45") (pin "P$2") (pinfunction "S_P$2") (pintype "passive"))
    )
    (net (code "6") (name "BOOT_FLASH") (class "Default")
      (node (ref "IC5") (pin "60") (pinfunction "BOOT0_60") (pintype "bidirectional"))
      (node (ref "R13") (pin "2") (pinfunction "2_2") (pintype "passive"))
      (node (ref "SW4") (pin "A") (pinfunction "P_A") (pintype "passive"))
      (node (ref "SW4") (pin "A'") (pinfunction "P1_A'") (pintype "passive"))
    )
    (net (code "7") (name "DENSITY_CV") (class "Default")
      (node (ref "C22") (pin "2") (pinfunction "2_2") (pintype "passive"))
      (node (ref "IC3") (pin "1") (pinfunction "OUT_1") (pintype "output"))
      (node (ref "IC5") (pin "17") (pinfunction "PA3/USART2_RX/ADC3/TIM2_CH4_17") (pintype "bidirectional"))
      (node (ref "R31") (pin "1") (pinfunction "1_1") (pintype "passive"))
    )
    (net (code "8") (name "GND") (class "Default")
      (node (ref "C1") (pin "-") (pinfunction "-_-") (pintype "passive"))
      (node (ref "C12") (pin "2") (pinfunction "2_2") (pintype "passive"))
      (node (ref "C13") (pin "+") (pinfunction "+_+") (pintype "passive"))
      (node (ref "C14") (pin "2") (pinfunction "2_2") (pintype "passive"))
      (node (ref "C15") (pin "2") (pinfunction "2_2") (pintype "passive"))
      (node (ref "C16") (pin "2") (pinfunction "2_2") (pintype "passive"))
      (node (ref "C17") (pin "2") (pinfunction "2_2") (pintype "passive"))
      (node (ref "C18") (pin "2") (pinfunction "2_2") (pintype "passive"))
      (node (ref "C19") (pin "2") (pinfunction "2_2") (pintype "passive"))
      (node (ref "C2") (pin "-") (pinfunction "-_-") (pintype "passive"))
      (node (ref "C23") (pin "2") (pinfunction "2_2") (pintype "passive"))
      (node (ref "C24") (pin "2") (pinfunction "2_2") (pintype "passive"))
      (node (ref "C25") (pin "2") (pinfunction "2_2") (pintype "passive"))
      (node (ref "C26") (pin "2") (pinfunction "2_2") (pintype "passive"))
      (node (ref "C27") (pin "-") (pinfunction "-_-") (pintype "passive"))
      (node (ref "C28") (pin "-") (pinfunction "-_-") (pintype "passive"))
      (node (ref "C29") (pin "2") (pinfunction "2_2") (pintype "passive"))
      (node (ref "C3") (pin "2") (pinfunction "2_2") (pintype "passive"))
      (node (ref "C30") (pin "2") (pinfunction "2_2") (pintype "passive"))
      (node (ref "C31") (pin "-") (pinfunction "-_-") (pintype "passive"))
      (node (ref "C32") (pin "2") (pinfunction "2_2") (pintype "passive"))
      (node (ref "C34") (pin "2") (pinfunction "2_2") (pintype "passive"))
      (node (ref "C35") (pin "-") (pinfunction "-_-") (pintype "passive"))
      (node (ref "C38") (pin "2") (pinfunction "2_2") (pintype "passive"))
      (node (ref "C39") (pin "2") (pinfunction "2_2") (pintype "passive"))
      (node (ref "C4") (pin "-") (pinfunction "-_-") (pintype "passive"))
      (node (ref "C43") (pin "2") (pinfunction "2_2") (pintype "passive"))
      (node (ref "C44") (pin "2") (pinfunction "2_2") (pintype "passive"))
      (node (ref "C45") (pin "1") (pinfunction "1_1") (pintype "passive"))
      (node (ref "C46") (pin "1") (pinfunction "1_1") (pintype "passive"))
      (node (ref "C47") (pin "1") (pinfunction "1_1") (pintype "passive"))
      (node (ref "C48") (pin "1") (pinfunction "1_1") (pintype "passive"))
      (node (ref "C49") (pin "-") (pinfunction "-_-") (pintype "passive"))
      (node (ref "C5") (pin "2") (pinfunction "2_2") (pintype "passive"))
      (node (ref "C50") (pin "2") (pinfunction "2_2") (pintype "passive"))
      (node (ref "C6") (pin "1") (pinfunction "1_1") (pintype "passive"))
      (node (ref "C7") (pin "1") (pinfunction "1_1") (pintype "passive"))
      (node (ref "C8") (pin "2") (pinfunction "2_2") (pintype "passive"))
      (node (ref "IC1") (pin "13") (pinfunction "G_13") (pintype "input"))
      (node (ref "IC1") (pin "8") (pinfunction "GND_8") (pintype "power_in"))
      (node (ref "IC10") (pin "3") (pinfunction "+IN_3") (pintype "input"))
      (node (ref "IC10") (pin "5") (pinfunction "+IN_5") (pintype "input"))
      (node (ref "IC2") (pin "1") (pinfunction "GND_1") (pintype "power_in"))
      (node (ref "IC3") (pin "3") (pinfunction "+IN_3") (pintype "input"))
      (node (ref "IC3") (pin "4") (pinfunction "V-_4") (pintype "power_in"))
      (node (ref "IC3") (pin "5") (pinfunction "+IN_5") (pintype "input"))
      (node (ref "IC4") (pin "10") (pinfunction "+IN_10") (pintype "input"))
      (node (ref "IC4") (pin "11") (pinfunction "V-_11") (pintype "power_in"))
      (node (ref "IC4") (pin "12") (pinfunction "+IN_12") (pintype "input"))
      (node (ref "IC4") (pin "3") (pinfunction "+IN_3") (pintype "input"))
      (node (ref "IC4") (pin "5") (pinfunction "+IN_5") (pintype "input"))
      (node (ref "IC5") (pin "12") (pinfunction "VSSA_12") (pintype "power_in"))
      (node (ref "IC5") (pin "18") (pinfunction "VSS_4_18") (pintype "power_in"))
      (node (ref "IC5") (pin "26") (pinfunction "PB0/ADC8/TIM3_CH3_26") (pintype "bidirectional"))
      (node (ref "IC5") (pin "28") (pinfunction "PB2/BOOT1_28") (pintype "bidirectional"))
      (node (ref "IC5") (pin "63") (pinfunction "VSS_3_63") (pintype "power_in"))
      (node (ref "IC6") (pin "1") (pinfunction "C_1") (pintype "passive"))
      (node (ref "IC7") (pin "1") (pinfunction "GND_1") (pintype "power_in"))
      (node (ref "IC8") (pin "11") (pinfunction "HPGND_11") (pintype "bidirectional"))
      (node (ref "IC8") (pin "15") (pinfunction "AGND_15") (pintype "bidirectional"))
      (node (ref "IC8") (pin "21") (pinfunction "MODE_21") (pintype "bidirectional"))
      (node (ref "IC8") (pin "22") (pinfunction "CSB_22") (pintype "bidirectional"))
      (node (ref "IC8") (pin "28") (pinfunction "DGND_28") (pintype "bidirectional"))
      (node (ref "IC9") (pin "3") (pinfunction "+IN_3") (pintype "input"))
      (node (ref "IC9") (pin "5") (pinfunction "+IN_5") (pintype "input"))
      (node (ref "J1") (pin "P1") (pinfunction "1_P1") (pintype "passive"))
      (node (ref "J1") (pin "P2") (pinfunction "2_P2") (pintype "passive"))
      (node (ref "J10") (pin "P1") (pinfunction "1_P1") (pintype "passive"))
      (node (ref "J11") (pin "P1") (pinfunction "1_P1") (pintype "passive"))
      (node (ref "J12") (pin "P1") (pinfunction "1_P1") (pintype "passive"))
      (node (ref "J2") (pin "P1") (pinfunction "1_P1") (pintype "passive"))
      (node (ref "J2") (pin "P2") (pinfunction "2_P2") (pintype "passive"))
      (node (ref "J3") (pin "P1") (pinfunction "1_P1") (pintype "passive"))
      (node (ref "J4") (pin "P1") (pinfunction "1_P1") (pintype "passive"))
      (node (ref "J5") (pin "P1") (pinfunction "1_P1") (pintype "passive"))
      (node (ref "J6") (pin "P1") (pinfunction "1_P1") (pintype "passive"))
      (node (ref "J7") (pin "P1") (pinfunction "1_P1") (pintype "passive"))
      (node (ref "J8") (pin "P1") (pinfunction "1_P1") (pintype "passive"))
      (node (ref "J9") (pin "P1") (pinfunction "1_P1") (pintype "passive"))
      (node (ref "JP1") (pin "1") (pinfunction "1_1") (pintype "passive"))
      (node (ref "JP2") (pin "3") (pinfunction "3_3") (pintype "passive"))
      (node (ref "JP2") (pin "5") (pinfunction "5_5") (pintype "passive"))
      (node (ref "JP2") (pin "9") (pinfunction "9_9") (pintype "passive"))
      (node (ref "JP3") (pin "3") (pinfunction "3_3") (pintype "passive"))
      (node (ref "JP3") (pin "4") (pinfunction "4_4") (pintype "passive"))
      (node (ref "JP3") (pin "5") (pinfunction "5_5") (pintype "passive"))
      (node (ref "JP3") (pin "6") (pinfunction "6_6") (pintype "passive"))
      (node (ref "JP3") (pin "7") (pinfunction "7_7") (pintype "passive"))
      (node (ref "JP3") (pin "8") (pinfunction "8_8") (pintype "passive"))
      (node (ref "LED1") (pin "2") (pinfunction "C_2") (pintype "bidirectional"))
      (node (ref "LED2") (pin "2") (pinfunction "C_2") (pintype "bidirectional"))
      (node (ref "LED3") (pin "2") (pinfunction "C_2") (pintype "bidirectional"))
      (node (ref "LED4") (pin "2") (pinfunction "C_2") (pintype "bidirectional"))
      (node (ref "Q1") (pin "E") (pinfunction "E_E") (pintype "passive"))
      (node (ref "Q2") (pin "E") (pinfunction "E_E") (pintype "passive"))
      (node (ref "R13") (pin "1") (pinfunction "1_1") (pintype "passive"))
      (node (ref "R18") (pin "P$1") (pinfunction "E_P$1") (pintype "passive"))
      (node (ref "R19") (pin "P$3") (pinfunction "A_P$3") (pintype "passive"))
      (node (ref "R20") (pin "P$3") (pinfunction "A_P$3") (pintype "passive"))
      (node (ref "R43") (pin "P$1") (pinfunction "E_P$1") (pintype "passive"))
      (node (ref "R44") (pin "P$3") (pinfunction "A_P$3") (pintype "passive"))
      (node (ref "R45") (pin "P$3") (pinfunction "A_P$3") (pintype "passive"))
      (node (ref "R50") (pin "1") (pinfunction "1_1") (pintype "passive"))
      (node (ref "R54") (pin "1") (pinfunction "1_1") (pintype "passive"))
      (node (ref "R56") (pin "1") (pinfunction "1_1") (pintype "passive"))
      (node (ref "R59") (pin "1") (pinfunction "1_1") (pintype "passive"))
      (node (ref "SW1") (pin "L2") (pinfunction "L2_L2") (pintype "passive"))
      (node (ref "SW1") (pin "P3") (pinfunction "A3_P3") (pintype "passive"))
      (node (ref "SW1") (pin "P6") (pinfunction "B3_P6") (pintype "passive"))
      (node (ref "SW2") (pin "1") (pinfunction "1_1") (pintype "passive"))
      (node (ref "SW2") (pin "2") (pinfunction "2_2") (pintype "passive"))
      (node (ref "SW3") (pin "1") (pinfunction "1_1") (pintype "passive"))
      (node (ref "SW3") (pin "2") (pinfunction "2_2") (pintype "passive"))
      (node (ref "SW5") (pin "A") (pinfunction "P_A") (pintype "passive"))
      (node (ref "SW5") (pin "A'") (pinfunction "P1_A'") (pintype "passive"))
    )
    (net (code "9") (name "I2C_SCL") (class "Default")
      (node (ref "IC5") (pin "29") (pinfunction "PB10/SPI2_SCK/I2S_SCK/I2C2_SCL/USART3_TX_29") (pintype "bidirectional"))
      (node (ref "IC8") (pin "24") (pinfunction "SCLK_24") (pintype "bidirectional"))
      (node (ref "R40") (pin "1") (pinfunction "1_1") (pintype "passive"))
    )
    (net (code "10") (name "I2C_SDA") (class "Default")
      (node (ref "IC5") (pin "30") (pinfunction "PB11/I2C2_SDA/USART3_RX_30") (pintype "bidirectional"))
      (node (ref "IC8") (pin "23") (pinfunction "SDIN_23") (pintype "bidirectional"))
      (node (ref "R41") (pin "1") (pinfunction "1_1") (pintype "passive"))
    )
    (net (code "11") (name "I2S_LRCK") (class "Default")
      (node (ref "IC5") (pin "33") (pinfunction "PB12/SPI2_NSS/I2S2_WS/I2C2_SMBA/USART3_CK/TIM1_BKIN_33") (pintype "bidirectional"))
      (node (ref "IC8") (pin "5") (pinfunction "DACLRC_5") (pintype "bidirectional"))
      (node (ref "IC8") (pin "7") (pinfunction "ADCLRC_7") (pintype "bidirectional"))
    )
    (net (code "12") (name "I2S_SCK") (class "Default")
      (node (ref "IC5") (pin "34") (pinfunction "PB13/SPI2_SCK/I2S2_SCK/USART3_CTS/TIM1_CH1N_34") (pintype "bidirectional"))
      (node (ref "IC8") (pin "3") (pinfunction "BCLK_3") (pintype "bidirectional"))
    )
    (net (code "13") (name "I2S_SIN") (class "Default")
      (node (ref "IC5") (pin "35") (pinfunction "PB14/SPI2_MISO/USART3_RTS/TIM1_CH2N_35") (pintype "bidirectional"))
      (node (ref "IC8") (pin "6") (pinfunction "ADCDAT_6") (pintype "bidirectional"))
    )
    (net (code "14") (name "I2S_SOUT") (class "Default")
      (node (ref "IC5") (pin "36") (pinfunction "PB15/SPI2_MOSI/I2S2_SD/TIM1_CH3N_36") (pintype "bidirectional"))
      (node (ref "IC8") (pin "4") (pinfunction "DACDAT_4") (pintype "bidirectional"))
    )
    (net (code "15") (name "JTCK") (class "Default")
      (node (ref "IC5") (pin "49") (pinfunction "PA14/JTCK-SWCLK_49") (pintype "bidirectional"))
      (node (ref "JP2") (pin "4") (pinfunction "4_4") (pintype "passive"))
    )
    (net (code "16") (name "JTDI") (class "Default")
      (node (ref "IC5") (pin "50") (pinfunction "PA15/JTDI/SPI3_NSS/I2S3_WS_50") (pintype "bidirectional"))
      (node (ref "JP2") (pin "8") (pinfunction "8_8") (pintype "passive"))
    )
    (net (code "17") (name "JTDO") (class "Default")
      (node (ref "IC5") (pin "55") (pinfunction "PB3/JTDO/SPI3_SCK/I2S3_SCK_55") (pintype "bidirectional"))
      (node (ref "JP2") (pin "6") (pinfunction "6_6") (pintype "passive"))
    )
    (net (code "18") (name "JTMS") (class "Default")
      (node (ref "IC5") (pin "46") (pinfunction "PA13/JTMS-SWDAT_46") (pintype "bidirectional"))
      (node (ref "JP2") (pin "2") (pinfunction "2_2") (pintype "passive"))
    )
    (net (code "19") (name "LED_DATA") (class "Default")
      (node (ref "IC1") (pin "14") (pinfunction "SER_14") (pintype "input"))
      (node (ref "IC5") (pin "57") (pinfunction "PB5/I2C1_SMBA/SPI1_MOSI/SPI3_MOSI/I2S3_SD_57") (pintype "bidirectional"))
    )
    (net (code "20") (name "LED_EN") (class "Default")
      (node (ref "IC1") (pin "12") (pinfunction "RCK_12") (pintype "input"))
      (node (ref "IC5") (pin "24") (pinfunction "PC4/ADC14_24") (pintype "bidirectional"))
    )
    (net (code "21") (name "LED_REC") (class "Default")
      (node (ref "IC5") (pin "62") (pinfunction "PB9/SPI2_NSS/I2S2_WS/I2C1_SDA/TIM4_CH4_62") (pintype "bidirectional"))
      (node (ref "R1") (pin "1") (pinfunction "1_1") (pintype "passive"))
      (node (ref "R2") (pin "1") (pinfunction "1_1") (pintype "passive"))
    )
    (net (code "22") (name "LED_SCK") (class "Default")
      (node (ref "IC1") (pin "11") (pinfunction "SCK_11") (pintype "input"))
      (node (ref "IC5") (pin "25") (pinfunction "PC5/ADC15_25") (pintype "bidirectional"))
    )
    (net (code "23") (name "LIN") (class "Default")
      (node (ref "C37") (pin "+") (pinfunction "+_+") (pintype "passive"))
      (node (ref "IC8") (pin "20") (pinfunction "LLINEIN_20") (pintype "bidirectional"))
    )
    (net (code "24") (name "LOUT") (class "Default")
      (node (ref "C33") (pin "+") (pinfunction "+_+") (pintype "passive"))
      (node (ref "IC8") (pin "12") (pinfunction "LOUT_12") (pintype "bidirectional"))
    )
    (net (code "25") (name "Net-(C33-Pad-)") (class "Default")
      (node (ref "C33") (pin "-") (pinfunction "-_-") (pintype "passive"))
      (node (ref "R51") (pin "2") (pinfunction "2_2") (pintype "passive"))
      (node (ref "R59") (pin "2") (pinfunction "2_2") (pintype "passive"))
    )
    (net (code "26") (name "Net-(C36-Pad-)") (class "Default")
      (node (ref "C36") (pin "-") (pinfunction "-_-") (pintype "passive"))
      (node (ref "C43") (pin "1") (pinfunction "1_1") (pintype "passive"))
      (node (ref "R53") (pin "1") (pinfunction "1_1") (pintype "passive"))
      (node (ref "R54") (pin "2") (pinfunction "2_2") (pintype "passive"))
    )
    (net (code "27") (name "Net-(C37-Pad-)") (class "Default")
      (node (ref "C37") (pin "-") (pinfunction "-_-") (pintype "passive"))
      (node (ref "C44") (pin "1") (pinfunction "1_1") (pintype "passive"))
      (node (ref "R55") (pin "1") (pinfunction "1_1") (pintype "passive"))
      (node (ref "R56") (pin "2") (pinfunction "2_2") (pintype "passive"))
    )
    (net (code "28") (name "Net-(C41-Pad-)") (class "Default")
      (node (ref "C41") (pin "-") (pinfunction "-_-") (pintype "passive"))
      (node (ref "R50") (pin "2") (pinfunction "2_2") (pintype "passive"))
      (node (ref "R52") (pin "2") (pinfunction "2_2") (pintype "passive"))
    )
    (net (code "29") (name "Net-(D1-PadA)") (class "Default")
      (node (ref "D1") (pin "A") (pinfunction "A_A") (pintype "passive"))
      (node (ref "JP3") (pin "1") (pinfunction "1_1") (pintype "passive"))
      (node (ref "JP3") (pin "2") (pinfunction "2_2") (pintype "passive"))
    )
    (net (code "30") (name "Net-(D2-PadC)") (class "Default")
      (node (ref "D2") (pin "C") (pinfunction "C_C") (pintype "passive"))
      (node (ref "JP3") (pin "10") (pinfunction "10_10") (pintype "passive"))
      (node (ref "JP3") (pin "9") (pinfunction "9_9") (pintype "passive"))
    )
    (net (code "31") (name "Net-(IC1A-QA)") (class "Default")
      (node (ref "IC1") (pin "15") (pinfunction "QA_15") (pintype "tri_state"))
      (node (ref "R10") (pin "2") (pinfunction "2_2") (pintype "passive"))
    )
    (net (code "32") (name "Net-(IC1A-QB)") (class "Default")
      (node (ref "IC1") (pin "1") (pinfunction "QB_1") (pintype "tri_state"))
      (node (ref "R9") (pin "2") (pinfunction "2_2") (pintype "passive"))
    )
    (net (code "33") (name "Net-(IC1A-QC)") (class "Default")
      (node (ref "IC1") (pin "2") (pinfunction "QC_2") (pintype "tri_state"))
      (node (ref "R8") (pin "2") (pinfunction "2_2") (pintype "passive"))
    )
    (net (code "34") (name "Net-(IC1A-QD)") (class "Default")
      (node (ref "IC1") (pin "3") (pinfunction "QD_3") (pintype "tri_state"))
      (node (ref "R7") (pin "2") (pinfunction "2_2") (pintype "passive"))
    )
    (net (code "35") (name "Net-(IC1A-QE)") (class "Default")
      (node (ref "IC1") (pin "4") (pinfunction "QE_4") (pintype "tri_state"))
      (node (ref "R6") (pin "2") (pinfunction "2_2") (pintype "passive"))
    )
    (net (code "36") (name "Net-(IC1A-QF)") (class "Default")
      (node (ref "IC1") (pin "5") (pinfunction "QF_5") (pintype "tri_state"))
      (node (ref "R5") (pin "2") (pinfunction "2_2") (pintype "passive"))
    )
    (net (code "37") (name "Net-(IC1A-QG)") (class "Default")
      (node (ref "IC1") (pin "6") (pinfunction "QG_6") (pintype "tri_state"))
      (node (ref "R3") (pin "2") (pinfunction "2_2") (pintype "passive"))
    )
    (net (code "38") (name "Net-(IC1A-QH)") (class "Default")
      (node (ref "IC1") (pin "7") (pinfunction "QH_7") (pintype "tri_state"))
      (node (ref "R4") (pin "2") (pinfunction "2_2") (pintype "passive"))
    )
    (net (code "39") (name "Net-(IC2-VIN)") (class "Default")
      (node (ref "C2") (pin "+") (pinfunction "+_+") (pintype "passive"))
      (node (ref "IC2") (pin "2") (pinfunction "VIN_2") (pintype "input"))
      (node (ref "R11") (pin "2") (pinfunction "2_2") (pintype "passive"))
    )
    (net (code "40") (name "Net-(IC3A--IN)") (class "Default")
      (node (ref "C22") (pin "1") (pinfunction "1_1") (pintype "passive"))
      (node (ref "IC3") (pin "2") (pinfunction "-IN_2") (pintype "input"))
      (node (ref "R31") (pin "2") (pinfunction "2_2") (pintype "passive"))
      (node (ref "R32") (pin "1") (pinfunction "1_1") (pintype "passive"))
      (node (ref "R33") (pin "1") (pinfunction "1_1") (pintype "passive"))
    )
    (net (code "41") (name "Net-(IC3B--IN)") (class "Default")
      (node (ref "C9") (pin "1") (pinfunction "1_1") (pintype "passive"))
      (node (ref "IC3") (pin "6") (pinfunction "-IN_6") (pintype "input"))
      (node (ref "R27") (pin "2") (pinfunction "2_2") (pintype "passive"))
      (node (ref "R28") (pin "1") (pinfunction "1_1") (pintype "passive"))
      (node (ref "R29") (pin "1") (pinfunction "1_1") (pintype "passive"))
    )
    (net (code "42") (name "Net-(IC4A--IN)") (class "Default")
      (node (ref "C20") (pin "1") (pinfunction "1_1") (pintype "passive"))
      (node (ref "IC4") (pin "2") (pinfunction "-IN_2") (pintype "input"))
      (node (ref "R34") (pin "2") (pinfunction "2_2") (pintype "passive"))
      (node (ref "R36") (pin "1") (pinfunction "1_1") (pintype "passive"))
      (node (ref "R38") (pin "1") (pinfunction "1_1") (pintype "passive"))
    )
    (net (code "43") (name "Net-(IC4B--IN)") (class "Default")
      (node (ref "C21") (pin "1") (pinfunction "1_1") (pintype "passive"))
      (node (ref "IC4") (pin "6") (pinfunction "-IN_6") (pintype "input"))
      (node (ref "R35") (pin "2") (pinfunction "2_2") (pintype "passive"))
      (node (ref "R37") (pin "1") (pinfunction "1_1") (pintype "passive"))
      (node (ref "R39") (pin "1") (pinfunction "1_1") (pintype "passive"))
    )
    (net (code "44") (name "Net-(IC4C--IN)") (class "Default")
      (node (ref "C11") (pin "1") (pinfunction "1_1") (pintype "passive"))
      (node (ref "IC4") (pin "9") (pinfunction "-IN_9") (pintype "input"))
      (node (ref "R23") (pin "1") (pinfunction "1_1") (pintype "passive"))
      (node (ref "R24") (pin "1") (pinfunction "1_1") (pintype "passive"))
      (node (ref "R26") (pin "2") (pinfunction "2_2") (pintype "passive"))
    )
    (net (code "45") (name "Net-(IC4D--IN)") (class "Default")
      (node (ref "C10") (pin "1") (pinfunction "1_1") (pintype "passive"))
      (node (ref "IC4") (pin "13") (pinfunction "-IN_13") (pintype "input"))
      (node (ref "R21") (pin "1") (pinfunction "1_1") (pintype "passive"))
      (node (ref "R22") (pin "1") (pinfunction "1_1") (pintype "passive"))
      (node (ref "R25") (pin "2") (pinfunction "2_2") (pintype "passive"))
    )
    (net (code "46") (name "Net-(IC5-PD0{slash}OSC_IN)") (class "Default")
      (node (ref "C7") (pin "2") (pinfunction "2_2") (pintype "passive"))
      (node (ref "IC5") (pin "5") (pinfunction "PD0/OSC_IN_5") (pintype "bidirectional"))
      (node (ref "Q3") (pin "2") (pinfunction "2_2") (pintype "passive"))
    )
    (net (code "47") (name "Net-(IC5-PD1{slash}OSC_OUT)") (class "Default")
      (node (ref "C6") (pin "2") (pinfunction "2_2") (pintype "passive"))
      (node (ref "IC5") (pin "6") (pinfunction "PD1/OSC_OUT_6") (pintype "bidirectional"))
      (node (ref "Q3") (pin "1") (pinfunction "1_1") (pintype "passive"))
    )
    (net (code "48") (name "Net-(IC5-VCAP_1)") (class "Default")
      (node (ref "C24") (pin "1") (pinfunction "1_1") (pintype "passive"))
      (node (ref "IC5") (pin "31") (pinfunction "VCAP_1_31") (pintype "power_in"))
    )
    (net (code "49") (name "Net-(IC5-VCAP_2)") (class "Default")
      (node (ref "C19") (pin "1") (pinfunction "1_1") (pintype "passive"))
      (node (ref "IC5") (pin "47") (pinfunction "VCAP_2_47") (pintype "power_in"))
    )
    (net (code "50") (name "Net-(IC8-VMID)") (class "Default")
      (node (ref "C34") (pin "1") (pinfunction "1_1") (pintype "passive"))
      (node (ref "C35") (pin "+") (pinfunction "+_+") (pintype "passive"))
      (node (ref "IC8") (pin "16") (pinfunction "VMID_16") (pintype "bidirectional"))
    )
    (net (code "51") (name "Net-(IC8-XTI{slash}MCLK)") (class "Default")
      (node (ref "C48") (pin "2") (pinfunction "2_2") (pintype "passive"))
      (node (ref "IC8") (pin "25") (pinfunction "XTI/MCLK_25") (pintype "bidirectional"))
      (node (ref "Q4") (pin "2") (pinfunction "2_2") (pintype "passive"))
    )
    (net (code "52") (name "Net-(IC8-XTO)") (class "Default")
      (node (ref "C47") (pin "2") (pinfunction "2_2") (pintype "passive"))
      (node (ref "IC8") (pin "26") (pinfunction "XTO_26") (pintype "bidirectional"))
      (node (ref "Q4") (pin "1") (pinfunction "1_1") (pintype "passive"))
    )
    (net (code "53") (name "Net-(IC9A--IN)") (class "Default")
      (node (ref "IC9") (pin "2") (pinfunction "-IN_2") (pintype "input"))
      (node (ref "R46") (pin "2") (pinfunction "2_2") (pintype "passive"))
      (node (ref "R57") (pin "1") (pinfunction "1_1") (pintype "passive"))
    )
    (net (code "54") (name "Net-(IC9A-OUT)") (class "Default")
      (node (ref "IC9") (pin "1") (pinfunction "OUT_1") (pintype "output"))
      (node (ref "R42") (pin "2") (pinfunction "S_2") (pintype "passive"))
      (node (ref "R42") (pin "3") (pinfunction "E_3") (pintype "passive"))
      (node (ref "R55") (pin "2") (pinfunction "2_2") (pintype "passive"))
    )
    (net (code "55") (name "Net-(IC9B--IN)") (class "Default")
      (node (ref "IC9") (pin "6") (pinfunction "-IN_6") (pintype "input"))
      (node (ref "R47") (pin "2") (pinfunction "2_2") (pintype "passive"))
      (node (ref "R58") (pin "1") (pinfunction "1_1") (pintype "passive"))
    )
    (net (code "56") (name "Net-(IC9B-OUT)") (class "Default")
      (node (ref "IC9") (pin "7") (pinfunction "OUT_7") (pintype "output"))
      (node (ref "R42") (pin "2P") (pinfunction "S_2P") (pintype "passive"))
      (node (ref "R42") (pin "3P") (pinfunction "E_3P") (pintype "passive"))
      (node (ref "R53") (pin "2") (pinfunction "2_2") (pintype "passive"))
    )
    (net (code "57") (name "Net-(IC10A--IN)") (class "Default")
      (node (ref "C40") (pin "1") (pinfunction "1_1") (pintype "passive"))
      (node (ref "IC10") (pin "2") (pinfunction "-IN_2") (pintype "input"))
      (node (ref "R49") (pin "2") (pinfunction "2_2") (pintype "passive"))
      (node (ref "R51") (pin "1") (pinfunction "1_1") (pintype "passive"))
    )
    (net (code "58") (name "Net-(IC10A-OUT)") (class "Default")
      (node (ref "C40") (pin "2") (pinfunction "2_2") (pintype "passive"))
      (node (ref "IC10") (pin "1") (pinfunction "OUT_1") (pintype "output"))
      (node (ref "R49") (pin "1") (pinfunction "1_1") (pintype "passive"))
      (node (ref "R61") (pin "2") (pinfunction "2_2") (pintype "passive"))
    )
    (net (code "59") (name "Net-(IC10B--IN)") (class "Default")
      (node (ref "C42") (pin "1") (pinfunction "1_1") (pintype "passive"))
      (node (ref "IC10") (pin "6") (pinfunction "-IN_6") (pintype "input"))
      (node (ref "R48") (pin "2") (pinfunction "2_2") (pintype "passive"))
      (node (ref "R52") (pin "1") (pinfunction "1_1") (pintype "passive"))
    )
    (net (code "60") (name "Net-(IC10B-OUT)") (class "Default")
      (node (ref "C42") (pin "2") (pinfunction "2_2") (pintype "passive"))
      (node (ref "IC10") (pin "7") (pinfunction "OUT_7") (pintype "output"))
      (node (ref "R48") (pin "1") (pinfunction "1_1") (pintype "passive"))
      (node (ref "R62") (pin "2") (pinfunction "2_2") (pintype "passive"))
    )
    (net (code "61") (name "Net-(J1-3)") (class "Default")
      (node (ref "J1") (pin "P3") (pinfunction "3_P3") (pintype "passive"))
      (node (ref "R12") (pin "1") (pinfunction "1_1") (pintype "passive"))
    )
    (net (code "62") (name "Net-(J2-3)") (class "Default")
      (node (ref "J2") (pin "P3") (pinfunction "3_P3") (pintype "passive"))
      (node (ref "R15") (pin "1") (pinfunction "1_1") (pintype "passive"))
    )
    (net (code "63") (name "Net-(J3-3)") (class "Default")
      (node (ref "J3") (pin "P3") (pinfunction "3_P3") (pintype "passive"))
      (node (ref "R29") (pin "2") (pinfunction "2_2") (pintype "passive"))
    )
    (net (code "64") (name "Net-(J4-3)") (class "Default")
      (node (ref "J4") (pin "P3") (pinfunction "3_P3") (pintype "passive"))
      (node (ref "R21") (pin "2") (pinfunction "2_2") (pintype "passive"))
    )
    (net (code "65") (name "Net-(J5-3)") (class "Default")
      (node (ref "J5") (pin "P3") (pinfunction "3_P3") (pintype "passive"))
      (node (ref "R38") (pin "2") (pinfunction "2_2") (pintype "passive"))
    )
    (net (code "66") (name "Net-(J6-3)") (class "Default")
      (node (ref "J6") (pin "P3") (pinfunction "3_P3") (pintype "passive"))
      (node (ref "R39") (pin "2") (pinfunction "2_2") (pintype "passive"))
    )
    (net (code "67") (name "Net-(J7-3)") (class "Default")
      (node (ref "J7") (pin "P3") (pinfunction "3_P3") (pintype "passive"))
      (node (ref "J8") (pin "P2") (pinfunction "2_P2") (pintype "passive"))
      (node (ref "R57") (pin "2") (pinfunction "2_2") (pintype "passive"))
    )
    (net (code "68") (name "Net-(J8-3)") (class "Default")
      (node (ref "J8") (pin "P3") (pinfunction "3_P3") (pintype "passive"))
      (node (ref "R58") (pin "2") (pinfunction "2_2") (pintype "passive"))
    )
    (net (code "69") (name "Net-(J9-3)") (class "Default")
      (node (ref "J9") (pin "P3") (pinfunction "3_P3") (pintype "passive"))
      (node (ref "R32") (pin "2") (pinfunction "2_2") (pintype "passive"))
    )
    (net (code "70") (name "Net-(J10-3)") (class "Default")
      (node (ref "J10") (pin "P3") (pinfunction "3_P3") (pintype "passive"))
      (node (ref "R24") (pin "2") (pinfunction "2_2") (pintype "passive"))
    )
    (net (code "71") (name "Net-(J11-3)") (class "Default")
      (node (ref "J11") (pin "P3") (pinfunction "3_P3") (pintype "passive"))
      (node (ref "R61") (pin "1") (pinfunction "1_1") (pintype "passive"))
    )
    (net (code "72") (name "Net-(J12-3)") (class "Default")
      (node (ref "J12") (pin "P3") (pinfunction "3_P3") (pintype "passive"))
      (node (ref "R62") (pin "1") (pinfunction "1_1") (pintype "passive"))
    )
    (net (code "73") (name "Net-(LED1-GRN)") (class "Default")
      (node (ref "LED1") (pin "3") (pinfunction "GRN_3") (pintype "bidirectional"))
      (node (ref "R4") (pin "1") (pinfunction "1_1") (pintype "passive"))
    )
    (net (code "74") (name "Net-(LED1-RED)") (class "Default")
      (node (ref "LED1") (pin "1") (pinfunction "RED_1") (pintype "bidirectional"))
      (node (ref "R3") (pin "1") (pinfunction "1_1") (pintype "passive"))
    )
    (net (code "75") (name "Net-(LED2-GRN)") (class "Default")
      (node (ref "LED2") (pin "3") (pinfunction "GRN_3") (pintype "bidirectional"))
      (node (ref "R5") (pin "1") (pinfunction "1_1") (pintype "passive"))
    )
    (net (code "76") (name "Net-(LED2-RED)") (class "Default")
      (node (ref "LED2") (pin "1") (pinfunction "RED_1") (pintype "bidirectional"))
      (node (ref "R6") (pin "1") (pinfunction "1_1") (pintype "passive"))
    )
    (net (code "77") (name "Net-(LED3-GRN)") (class "Default")
      (node (ref "LED3") (pin "3") (pinfunction "GRN_3") (pintype "bidirectional"))
      (node (ref "R7") (pin "1") (pinfunction "1_1") (pintype "passive"))
    )
    (net (code "78") (name "Net-(LED3-RED)") (class "Default")
      (node (ref "LED3") (pin "1") (pinfunction "RED_1") (pintype "bidirectional"))
      (node (ref "R8") (pin "1") (pinfunction "1_1") (pintype "passive"))
    )
    (net (code "79") (name "Net-(LED4-GRN)") (class "Default")
      (node (ref "LED4") (pin "3") (pinfunction "GRN_3") (pintype "bidirectional"))
      (node (ref "R9") (pin "1") (pinfunction "1_1") (pintype "passive"))
    )
    (net (code "80") (name "Net-(LED4-RED)") (class "Default")
      (node (ref "LED4") (pin "1") (pinfunction "RED_1") (pintype "bidirectional"))
      (node (ref "R10") (pin "1") (pinfunction "1_1") (pintype "passive"))
    )
    (net (code "81") (name "Net-(Q1-PadB)") (class "Default")
      (node (ref "Q1") (pin "B") (pinfunction "B_B") (pintype "passive"))
      (node (ref "R12") (pin "2") (pinfunction "2_2") (pintype "passive"))
    )
    (net (code "82") (name "Net-(Q2-PadB)") (class "Default")
      (node (ref "Q2") (pin "B") (pinfunction "B_B") (pintype "passive"))
      (node (ref "R15") (pin "2") (pinfunction "2_2") (pintype "passive"))
    )
    (net (code "83") (name "Net-(R1-Pad2)") (class "Default")
      (node (ref "R1") (pin "2") (pinfunction "2_2") (pintype "passive"))
      (node (ref "R2") (pin "2") (pinfunction "2_2") (pintype "passive"))
      (node (ref "SW1") (pin "L1") (pinfunction "L1_L1") (pintype "passive"))
    )
    (net (code "84") (name "Net-(R18-S)") (class "Default")
      (node (ref "R18") (pin "P$2") (pinfunction "S_P$2") (pintype "passive"))
      (node (ref "R28") (pin "2") (pinfunction "2_2") (pintype "passive"))
    )
    (net (code "85") (name "Net-(R42A-A)") (class "Default")
      (node (ref "R42") (pin "1P") (pinfunction "A_1P") (pintype "passive"))
      (node (ref "R47") (pin "1") (pinfunction "1_1") (pintype "passive"))
    )
    (net (code "86") (name "Net-(R42B-A)") (class "Default")
      (node (ref "R42") (pin "1") (pinfunction "A_1") (pintype "passive"))
      (node (ref "R46") (pin "1") (pinfunction "1_1") (pintype "passive"))
    )
    (net (code "87") (name "Net-(R43-S)") (class "Default")
      (node (ref "R33") (pin "2") (pinfunction "2_2") (pintype "passive"))
      (node (ref "R43") (pin "P$2") (pinfunction "S_P$2") (pintype "passive"))
    )
    (net (code "88") (name "PITCH_POT") (class "Default")
      (node (ref "IC5") (pin "9") (pinfunction "PC1/ADC11_9") (pintype "bidirectional"))
      (node (ref "R20") (pin "P$2") (pinfunction "S_P$2") (pintype "passive"))
    )
    (net (code "89") (name "PLAY") (class "Default")
      (node (ref "IC5") (pin "58") (pinfunction "PB6/I2C1_SCL/TIM4_CH1/USART1_TX_58") (pintype "bidirectional"))
      (node (ref "Q2") (pin "C") (pinfunction "C_C") (pintype "passive"))
      (node (ref "R16") (pin "1") (pinfunction "1_1") (pintype "passive"))
    )
    (net (code "90") (name "POSITION_POT_CV") (class "Default")
      (node (ref "C9") (pin "2") (pinfunction "2_2") (pintype "passive"))
      (node (ref "IC3") (pin "7") (pinfunction "OUT_7") (pintype "output"))
      (node (ref "IC5") (pin "16") (pinfunction "PA2/USART2_TX/ADC2/TIM2_CH3_16") (pintype "bidirectional"))
      (node (ref "R27") (pin "1") (pinfunction "1_1") (pintype "passive"))
    )
    (net (code "91") (name "REC") (class "Default")
      (node (ref "IC5") (pin "59") (pinfunction "PB7/I2C1_SDA/TIM4_CH2/USART1_RX_59") (pintype "bidirectional"))
      (node (ref "Q1") (pin "C") (pinfunction "C_C") (pintype "passive"))
      (node (ref "R14") (pin "1") (pinfunction "1_1") (pintype "passive"))
    )
    (net (code "92") (name "RESET") (class "Default")
      (node (ref "IC5") (pin "7") (pinfunction "NRST_7") (pintype "bidirectional"))
      (node (ref "JP2") (pin "10") (pinfunction "10_10") (pintype "passive"))
      (node (ref "R17") (pin "1") (pinfunction "1_1") (pintype "passive"))
      (node (ref "SW5") (pin "B") (pinfunction "S_B") (pintype "passive"))
      (node (ref "SW5") (pin "B'") (pinfunction "S1_B'") (pintype "passive"))
    )
    (net (code "93") (name "RIN") (class "Default")
      (node (ref "C36") (pin "+") (pinfunction "+_+") (pintype "passive"))
      (node (ref "IC8") (pin "19") (pinfunction "RLINEIN_19") (pintype "bidirectional"))
    )
    (net (code "94") (name "ROUT") (class "Default")
      (node (ref "C41") (pin "+") (pinfunction "+_+") (pintype "passive"))
      (node (ref "IC8") (pin "13") (pinfunction "ROUT_13") (pintype "bidirectional"))
    )
    (net (code "95") (name "RX") (class "Default")
      (node (ref "IC5") (pin "43") (pinfunction "PA10/USART1_RX/TIM1_CH3_43") (pintype "bidirectional"))
      (node (ref "JP1") (pin "4") (pinfunction "4_4") (pintype "passive"))
    )
    (net (code "96") (name "SIZE_CV") (class "Default")
      (node (ref "C10") (pin "2") (pinfunction "2_2") (pintype "passive"))
      (node (ref "IC4") (pin "14") (pinfunction "OUT_14") (pintype "output"))
      (node (ref "IC5") (pin "15") (pinfunction "PA1/USART2_RTS/UART4_RX/ADC1/TIM2_CH2_15") (pintype "bidirectional"))
      (node (ref "R25") (pin "1") (pinfunction "1_1") (pintype "passive"))
    )
    (net (code "97") (name "SIZE_POT") (class "Default")
      (node (ref "IC5") (pin "8") (pinfunction "PC0/ADC10_8") (pintype "bidirectional"))
      (node (ref "R19") (pin "P$2") (pinfunction "S_P$2") (pintype "passive"))
    )
    (net (code "98") (name "SW_LOAD") (class "Default")
      (node (ref "IC5") (pin "51") (pinfunction "PC10/SPI3_SCK/I2S3_SCK/UART4_TX_51") (pintype "bidirectional"))
      (node (ref "SW3") (pin "3") (pinfunction "3_3") (pintype "passive"))
      (node (ref "SW3") (pin "4") (pinfunction "4_4") (pintype "passive"))
    )
    (net (code "99") (name "SW_MODE") (class "Default")
      (node (ref "IC5") (pin "52") (pinfunction "PC11/UART4_RX/SPI3_MISO/USART3_RX_52") (pintype "bidirectional"))
      (node (ref "SW2") (pin "3") (pinfunction "3_3") (pintype "passive"))
      (node (ref "SW2") (pin "4") (pinfunction "4_4") (pintype "passive"))
    )
    (net (code "100") (name "SW_REC") (class "Default")
      (node (ref "IC5") (pin "61") (pinfunction "PB8/TIM4_CH3/I2C1_SCL_61") (pintype "bidirectional"))
      (node (ref "SW1") (pin "P2") (pinfunction "A2_P2") (pintype "passive"))
      (node (ref "SW1") (pin "P5") (pinfunction "B2_P5") (pintype "passive"))
    )
    (net (code "101") (name "TEXTURE_CV") (class "Default")
      (node (ref "C11") (pin "2") (pinfunction "2_2") (pintype "passive"))
      (node (ref "IC4") (pin "8") (pinfunction "OUT_8") (pintype "output"))
      (node (ref "IC5") (pin "14") (pinfunction "PA0-WKUP/USART2_CTS/UART4_TX/ADC0/TIM2_CH1_ETR_14") (pintype "bidirectional"))
      (node (ref "R26") (pin "1") (pinfunction "1_1") (pintype "passive"))
    )
    (net (code "102") (name "TEXTURE_POT") (class "Default")
      (node (ref "IC5") (pin "22") (pinfunction "PA6/SPI1_MISO/ADC6/TIM3_CH1_22") (pintype "bidirectional"))
      (node (ref "R44") (pin "P$2") (pinfunction "S_P$2") (pintype "passive"))
    )
    (net (code "103") (name "TX") (class "Default")
      (node (ref "IC5") (pin "42") (pinfunction "PA9/USART1_TX/TIM1_CH2_42") (pintype "bidirectional"))
      (node (ref "JP1") (pin "5") (pinfunction "5_5") (pintype "passive"))
    )
    (net (code "104") (name "VBAT") (class "Default")
      (node (ref "IC5") (pin "1") (pinfunction "VBAT_1") (pintype "power_in"))
    )
    (net (code "105") (name "VCC") (class "Default")
      (node (ref "C1") (pin "+") (pinfunction "+_+") (pintype "passive"))
      (node (ref "C38") (pin "1") (pinfunction "1_1") (pintype "passive"))
      (node (ref "C39") (pin "1") (pinfunction "1_1") (pintype "passive"))
      (node (ref "D1") (pin "C") (pinfunction "C_C") (pintype "passive"))
      (node (ref "IC10") (pin "8") (pinfunction "V+_8") (pintype "power_in"))
      (node (ref "IC7") (pin "3") (pinfunction "VIN_3") (pintype "input"))
      (node (ref "IC9") (pin "8") (pinfunction "V+_8") (pintype "power_in"))
      (node (ref "R11") (pin "1") (pinfunction "1_1") (pintype "passive"))
    )
    (net (code "106") (name "VEE") (class "Default")
      (node (ref "C13") (pin "-") (pinfunction "-_-") (pintype "passive"))
      (node (ref "C45") (pin "2") (pinfunction "2_2") (pintype "passive"))
      (node (ref "C46") (pin "2") (pinfunction "2_2") (pintype "passive"))
      (node (ref "D2") (pin "A") (pinfunction "A_A") (pintype "passive"))
      (node (ref "IC10") (pin "4") (pinfunction "V-_4") (pintype "power_in"))
      (node (ref "IC9") (pin "4") (pinfunction "V-_4") (pintype "power_in"))
      (node (ref "R30") (pin "1") (pinfunction "1_1") (pintype "passive"))
    )
    (net (code "107") (name "V_OCT") (class "Default")
      (node (ref "C20") (pin "2") (pinfunction "2_2") (pintype "passive"))
      (node (ref "IC4") (pin "1") (pinfunction "OUT_1") (pintype "output"))
      (node (ref "IC5") (pin "20") (pinfunction "PA4/SPI1_NSS/SPI3_NSS/USART2_CK/I2S3_WS/ADC4/DAC1_20") (pintype "bidirectional"))
      (node (ref "R34") (pin "1") (pinfunction "1_1") (pintype "passive"))
    )
    (net (code "108") (name "unconnected-(IC1A-QH*-Pad9)") (class "Default")
      (node (ref "IC1") (pin "9") (pinfunction "QH*_9") (pintype "tri_state"))
    )
    (net (code "109") (name "unconnected-(IC5-PA8{slash}USART1_CK{slash}TIM1_CH1{slash}MCO-Pad41)") (class "Default")
      (node (ref "IC5") (pin "41") (pinfunction "PA8/USART1_CK/TIM1_CH1/MCO_41") (pintype "bidirectional"))
    )
    (net (code "110") (name "unconnected-(IC5-PA11{slash}USART1_CTS{slash}CANRX{slash}USBDM{slash}TIM1_CH4-Pad44)") (class "Default")
      (node (ref "IC5") (pin "44") (pinfunction "PA11/USART1_CTS/CANRX/USBDM/TIM1_CH4_44") (pintype "bidirectional"))
    )
    (net (code "111") (name "unconnected-(IC5-PA12{slash}USART1_RTS{slash}CANTX{slash}USBDP{slash}TIM1_ETR-Pad45)") (class "Default")
      (node (ref "IC5") (pin "45") (pinfunction "PA12/USART1_RTS/CANTX/USBDP/TIM1_ETR_45") (pintype "bidirectional"))
    )
    (net (code "112") (name "unconnected-(IC5-PB1{slash}ADC9{slash}TIM3_CH4-Pad27)") (class "Default")
      (node (ref "IC5") (pin "27") (pinfunction "PB1/ADC9/TIM3_CH4_27") (pintype "bidirectional"))
    )
    (net (code "113") (name "unconnected-(IC5-PB4{slash}NJTRST{slash}SPI3_MISO{slash}SPI1_MISO-Pad56)") (class "Default")
      (node (ref "IC5") (pin "56") (pinfunction "PB4/NJTRST/SPI3_MISO/SPI1_MISO_56") (pintype "bidirectional"))
    )
    (net (code "114") (name "unconnected-(IC5-PC2{slash}SPI2_MISO{slash}ADC12-Pad10)") (class "Default")
      (node (ref "IC5") (pin "10") (pinfunction "PC2/SPI2_MISO/ADC12_10") (pintype "bidirectional"))
    )
    (net (code "115") (name "unconnected-(IC5-PC3{slash}SPI2_MOSI{slash}I2S2_SD{slash}ADC13-Pad11)") (class "Default")
      (node (ref "IC5") (pin "11") (pinfunction "PC3/SPI2_MOSI/I2S2_SD/ADC13_11") (pintype "bidirectional"))
    )
    (net (code "116") (name "unconnected-(IC5-PC6{slash}I2S2_MCK-Pad37)") (class "Default")
      (node (ref "IC5") (pin "37") (pinfunction "PC6/I2S2_MCK_37") (pintype "bidirectional"))
    )
    (net (code "117") (name "unconnected-(IC5-PC7{slash}I2S3_MCK-Pad38)") (class "Default")
      (node (ref "IC5") (pin "38") (pinfunction "PC7/I2S3_MCK_38") (pintype "bidirectional"))
    )
    (net (code "118") (name "unconnected-(IC5-PC8-Pad39)") (class "Default")
      (node (ref "IC5") (pin "39") (pinfunction "PC8_39") (pintype "bidirectional"))
    )
    (net (code "119") (name "unconnected-(IC5-PC9{slash}I2S2_CKIN{slash}I2S3_CKIN-Pad40)") (class "Default")
      (node (ref "IC5") (pin "40") (pinfunction "PC9/I2S2_CKIN/I2S3_CKIN_40") (pintype "bidirectional"))
    )
    (net (code "120") (name "unconnected-(IC5-PC12{slash}UART5_TX{slash}I2S3_SD{slash}USART3_CK-Pad53)") (class "Default")
      (node (ref "IC5") (pin "53") (pinfunction "PC12/UART5_TX/I2S3_SD/USART3_CK_53") (pintype "bidirectional"))
    )
    (net (code "121") (name "unconnected-(IC5-PC13-TAMPER-RTC-Pad2)") (class "Default")
      (node (ref "IC5") (pin "2") (pinfunction "PC13-TAMPER-RTC_2") (pintype "bidirectional"))
    )
    (net (code "122") (name "unconnected-(IC5-PC14{slash}OSC32_IN-Pad3)") (class "Default")
      (node (ref "IC5") (pin "3") (pinfunction "PC14/OSC32_IN_3") (pintype "bidirectional"))
    )
    (net (code "123") (name "unconnected-(IC5-PC15{slash}OSC_OUT-Pad4)") (class "Default")
      (node (ref "IC5") (pin "4") (pinfunction "PC15/OSC_OUT_4") (pintype "bidirectional"))
    )
    (net (code "124") (name "unconnected-(IC5-PD2{slash}TIM3-ETR-Pad54)") (class "Default")
      (node (ref "IC5") (pin "54") (pinfunction "PD2/TIM3-ETR_54") (pintype "bidirectional"))
    )
    (net (code "125") (name "unconnected-(IC8-CLKOUT-Pad2)") (class "Default")
      (node (ref "IC8") (pin "2") (pinfunction "CLKOUT_2") (pintype "bidirectional"))
    )
    (net (code "126") (name "unconnected-(IC8-LHPOUT-Pad9)") (class "Default")
      (node (ref "IC8") (pin "9") (pinfunction "LHPOUT_9") (pintype "bidirectional"))
    )
    (net (code "127") (name "unconnected-(IC8-MICBIAS-Pad17)") (class "Default")
      (node (ref "IC8") (pin "17") (pinfunction "MICBIAS_17") (pintype "bidirectional"))
    )
    (net (code "128") (name "unconnected-(IC8-MICIN-Pad18)") (class "Default")
      (node (ref "IC8") (pin "18") (pinfunction "MICIN_18") (pintype "bidirectional"))
    )
    (net (code "129") (name "unconnected-(IC8-RHPOUT-Pad10)") (class "Default")
      (node (ref "IC8") (pin "10") (pinfunction "RHPOUT_10") (pintype "bidirectional"))
    )
    (net (code "130") (name "unconnected-(J3-2-PadP2)") (class "Default")
      (node (ref "J3") (pin "P2") (pinfunction "2_P2") (pintype "passive"))
    )
    (net (code "131") (name "unconnected-(J4-2-PadP2)") (class "Default")
      (node (ref "J4") (pin "P2") (pinfunction "2_P2") (pintype "passive"))
    )
    (net (code "132") (name "unconnected-(J5-2-PadP2)") (class "Default")
      (node (ref "J5") (pin "P2") (pinfunction "2_P2") (pintype "passive"))
    )
    (net (code "133") (name "unconnected-(J6-2-PadP2)") (class "Default")
      (node (ref "J6") (pin "P2") (pinfunction "2_P2") (pintype "passive"))
    )
    (net (code "134") (name "unconnected-(J7-2-PadP2)") (class "Default")
      (node (ref "J7") (pin "P2") (pinfunction "2_P2") (pintype "passive"))
    )
    (net (code "135") (name "unconnected-(J9-2-PadP2)") (class "Default")
      (node (ref "J9") (pin "P2") (pinfunction "2_P2") (pintype "passive"))
    )
    (net (code "136") (name "unconnected-(J10-2-PadP2)") (class "Default")
      (node (ref "J10") (pin "P2") (pinfunction "2_P2") (pintype "passive"))
    )
    (net (code "137") (name "unconnected-(J11-2-PadP2)") (class "Default")
      (node (ref "J11") (pin "P2") (pinfunction "2_P2") (pintype "passive"))
    )
    (net (code "138") (name "unconnected-(J12-2-PadP2)") (class "Default")
      (node (ref "J12") (pin "P2") (pinfunction "2_P2") (pintype "passive"))
    )
    (net (code "139") (name "unconnected-(JP1-Pad2)") (class "Default")
      (node (ref "JP1") (pin "2") (pinfunction "2_2") (pintype "passive"))
    )
    (net (code "140") (name "unconnected-(JP1-Pad3)") (class "Default")
      (node (ref "JP1") (pin "3") (pinfunction "3_3") (pintype "passive"))
    )
    (net (code "141") (name "unconnected-(JP1-Pad6)") (class "Default")
      (node (ref "JP1") (pin "6") (pinfunction "6_6") (pintype "passive"))
    )
    (net (code "142") (name "unconnected-(JP2-Pad7)") (class "Default")
      (node (ref "JP2") (pin "7") (pinfunction "7_7") (pintype "passive"))
    )
    (net (code "143") (name "unconnected-(SW1A-A1-PadP1)") (class "Default")
      (node (ref "SW1") (pin "P1") (pinfunction "A1_P1") (pintype "passive"))
    )
    (net (code "144") (name "unconnected-(SW1A-B1-PadP4)") (class "Default")
      (node (ref "SW1") (pin "P4") (pinfunction "B1_P4") (pintype "passive"))
    )
  )
)
